# Inverter.net
KiCad netlist of a schematic drawn in Altium Designer
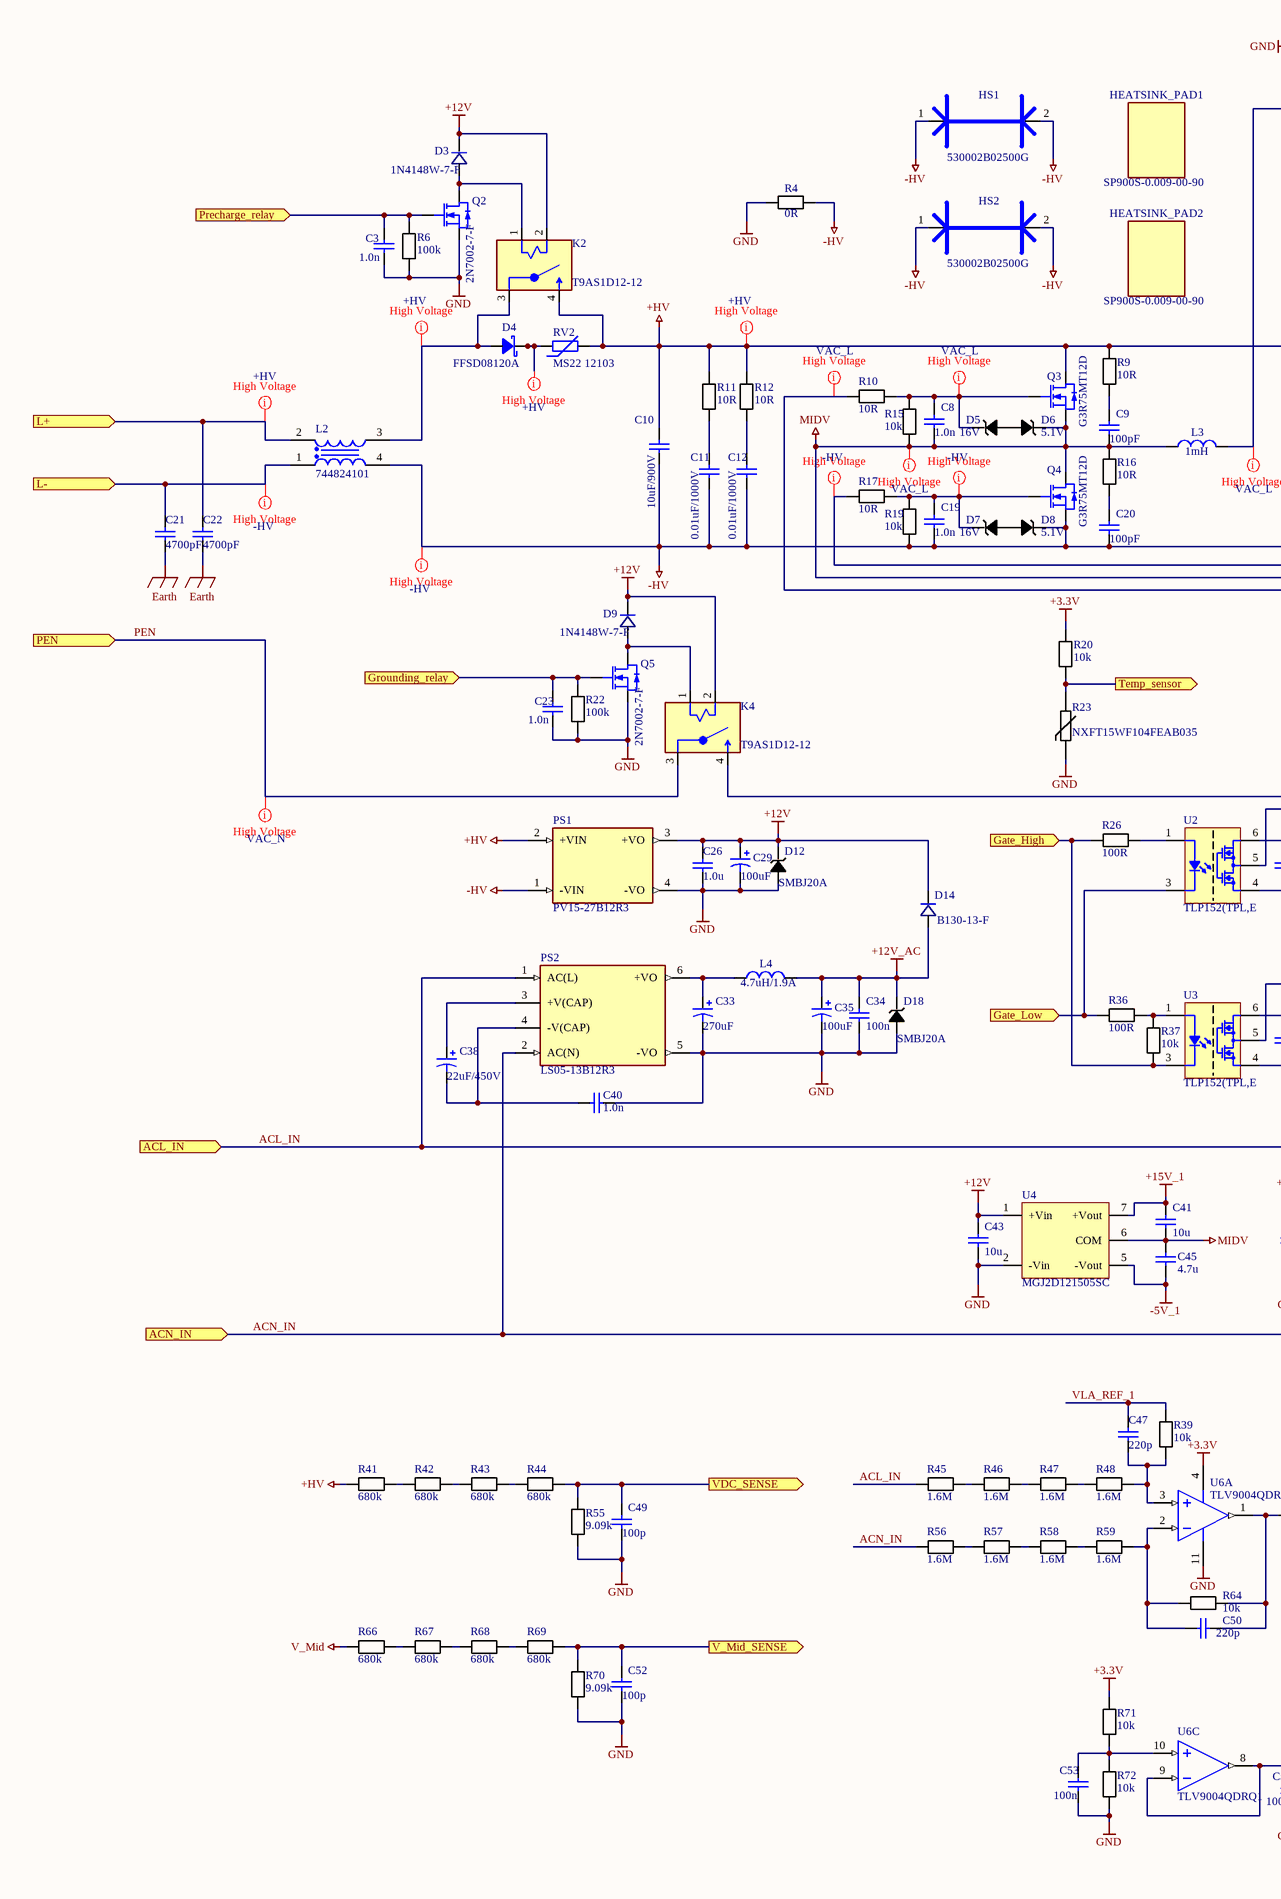
[diagram p0: Inverter.SchDoc, left]
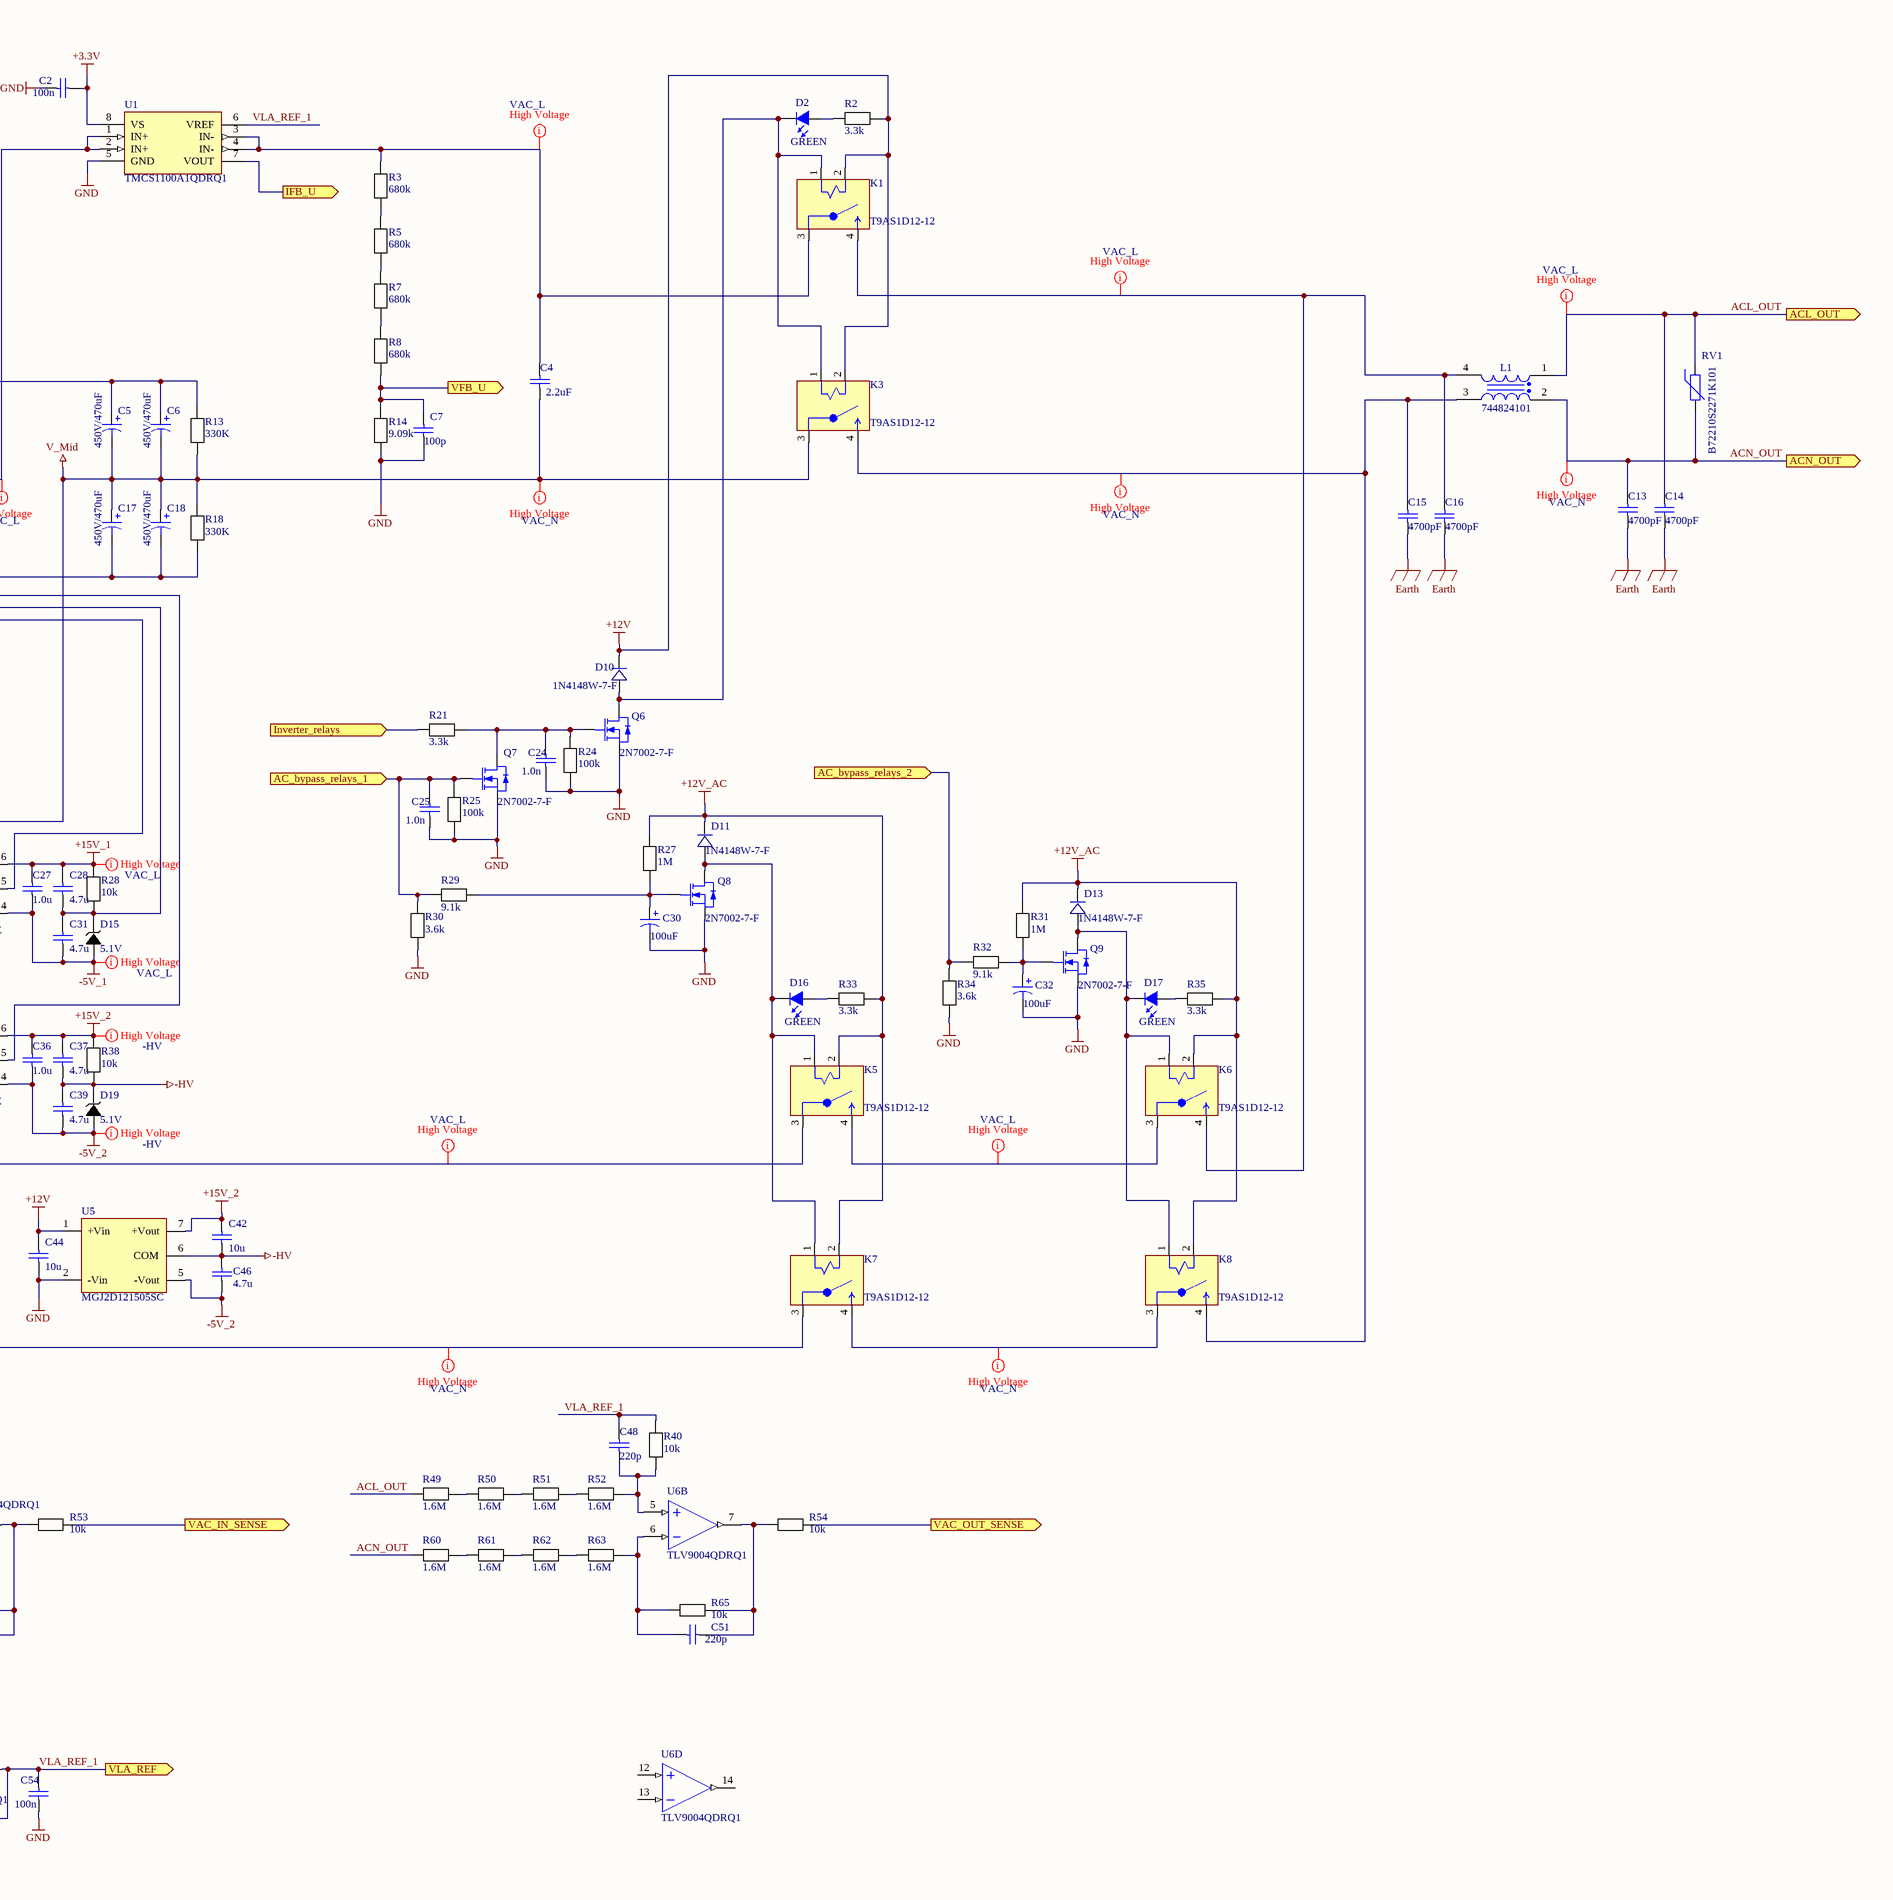
[diagram p1: Inverter.SchDoc, right]

(export (version "E")
  (design (tool "Eeschema 10.0.6"))
  (components
    (comp (ref "C2")
      (value "100n")
      (footprint "C0603")
      (description "Capacitor 100n 0603 +-10% 50V")
      (fields
        (field (name "PART NUMBER") "CAP_YAG_CC0603KRX7R9BB104_X7R")
        (field (name "MPN") "CC0603KRX7R9BB104")
      )
      (libsource (lib "Cap_Yag_0603_X7R_50_10%$") (part "CAP_YAG_CC0603KRX7R9BB104_X7R"))
    )
    (comp (ref "C3")
      (value "1.0n")
      (footprint "C0603")
      (description "Capacitor 1.0n 0603 +-10% 50V")
      (fields (field (name "PART NUMBER") "CAP_YAG_CC0603KRNPO9BN102_NPO") (field (name "MFR") "Yageo"))
      (libsource (lib "Cap_Yag_0603_NPO_50_10%$") (part "CAP_YAG_CC0603KRNPO9BN102_NPO"))
    )
    (comp (ref "C4")
      (value "2.2uF")
      (footprint "B32674")
      (fields (field (name "MPN") "B32674D6225K") (field (name "MFR") "EPCOS / TDK"))
      (libsource (lib "RCL") (part "CAP"))
    )
    (comp (ref "C5")
      (value "450V/470uF")
      (footprint "CAP_B43640B5477M000")
      (description "Aluminium Electrolytic Capacitors - Snap In 450VDC 470uF 20% PVC STD 6.3mm Term")
      (fields (field (name "MPN") "B43640B5477M000") (field (name "MFR") "EPCOS / TDK"))
      (libsource (lib "Miscellaneous Devices") (part "Cap Pol1"))
    )
    (comp (ref "C6")
      (value "450V/470uF")
      (footprint "CAP_B43640B5477M000")
      (description "Aluminium Electrolytic Capacitors - Snap In 450VDC 470uF 20% PVC STD 6.3mm Term")
      (fields (field (name "MPN") "B43640B5477M000") (field (name "MFR") "EPCOS / TDK"))
      (libsource (lib "Miscellaneous Devices") (part "Cap Pol1"))
    )
    (comp (ref "C7")
      (value "100p")
      (footprint "C0603")
      (description "Capacitor 100p 0603 +-10% 50V")
      (fields (field (name "PART NUMBER") "CAP_YAG_CC0603KRNPO9BN101_NPO") (field (name "MFR") "Yageo"))
      (libsource (lib "Cap_Yag_0603_NPO_50_10%$") (part "CAP_YAG_CC0603KRNPO9BN101_NPO"))
    )
    (comp (ref "C8")
      (value "1.0n")
      (footprint "C0603")
      (description "Capacitor 1.0n 0603 +-10% 50V")
      (fields (field (name "PART NUMBER") "CAP_YAG_CC0603KRNPO9BN102_NPO") (field (name "MFR") "Yageo"))
      (libsource (lib "Cap_Yag_0603_NPO_50_10%$") (part "CAP_YAG_CC0603KRNPO9BN102_NPO"))
    )
    (comp (ref "C9")
      (value "100pF")
      (footprint "C1210")
      (description "Capacitor 100p 1210 +-5% 1kV")
      (fields (field (name "MPN") "VJ1210A101JXGAT5Z") (field (name "MFR") "Vishay"))
      (libsource (lib "RCL") (part "CAP"))
    )
    (comp (ref "C10")
      (value "10uF/900V")
      (footprint "MKP1848C61090KK2")
      (description "CAP FILM 10UF 10% 900VDC")
      (fields (field (name "MPN") "MKP1848C61090KK2") (field (name "MFR") "Vishay / Roederstein"))
      (libsource (lib "RCL") (part "CAP"))
    )
    (comp (ref "C11")
      (value "0.01uF/1000V")
      (footprint "C1206")
      (description "0.01uF ±10% 1000V")
      (fields (field (name "MPN") "GRM31CR73A103KW03L") (field (name "MFR") "Murata"))
      (libsource (lib "RCL") (part "CAP"))
    )
    (comp (ref "C12")
      (value "0.01uF/1000V")
      (footprint "C1206")
      (description "0.01uF ±10% 1000V")
      (fields (field (name "MPN") "GRM31CR73A103KW03L") (field (name "MFR") "Murata"))
      (libsource (lib "RCL") (part "CAP"))
    )
    (comp (ref "C13")
      (value "4700pF")
      (footprint "CAP_C947U472MZVDBA7317")
      (description "4700pF ±20% 440VAC Ceramic Capacitor")
      (fields (field (name "MPN") "C947U472MZVDBA7317") (field (name "MFR") "KEMET"))
      (libsource (lib "RCL") (part "CAP"))
    )
    (comp (ref "C14")
      (value "4700pF")
      (footprint "CAP_C947U472MZVDBA7317")
      (description "4700pF ±20% 440VAC Ceramic Capacitor")
      (fields (field (name "MPN") "C947U472MZVDBA7317") (field (name "MFR") "KEMET"))
      (libsource (lib "RCL") (part "CAP"))
    )
    (comp (ref "C15")
      (value "4700pF")
      (footprint "CAP_C947U472MZVDBA7317")
      (description "4700pF ±20% 440VAC Ceramic Capacitor")
      (fields (field (name "MPN") "C947U472MZVDBA7317") (field (name "MFR") "KEMET"))
      (libsource (lib "RCL") (part "CAP"))
    )
    (comp (ref "C16")
      (value "4700pF")
      (footprint "CAP_C947U472MZVDBA7317")
      (description "4700pF ±20% 440VAC Ceramic Capacitor")
      (fields (field (name "MPN") "C947U472MZVDBA7317") (field (name "MFR") "KEMET"))
      (libsource (lib "RCL") (part "CAP"))
    )
    (comp (ref "C17")
      (value "450V/470uF")
      (footprint "CAP_B43640B5477M000")
      (description "Aluminium Electrolytic Capacitors - Snap In 450VDC 470uF 20% PVC STD 6.3mm Term")
      (fields (field (name "MPN") "B43640B5477M000") (field (name "MFR") "EPCOS / TDK"))
      (libsource (lib "Miscellaneous Devices") (part "Cap Pol1"))
    )
    (comp (ref "C18")
      (value "450V/470uF")
      (footprint "CAP_B43640B5477M000")
      (description "Aluminium Electrolytic Capacitors - Snap In 450VDC 470uF 20% PVC STD 6.3mm Term")
      (fields (field (name "MPN") "B43640B5477M000") (field (name "MFR") "EPCOS / TDK"))
      (libsource (lib "Miscellaneous Devices") (part "Cap Pol1"))
    )
    (comp (ref "C19")
      (value "1.0n")
      (footprint "C0603")
      (description "Capacitor 1.0n 0603 +-10% 50V")
      (fields (field (name "PART NUMBER") "CAP_YAG_CC0603KRNPO9BN102_NPO") (field (name "MFR") "Yageo"))
      (libsource (lib "Cap_Yag_0603_NPO_50_10%$") (part "CAP_YAG_CC0603KRNPO9BN102_NPO"))
    )
    (comp (ref "C20")
      (value "100pF")
      (footprint "C1210")
      (description "Capacitor 100p 1210 +-5% 1kV")
      (fields (field (name "MPN") "VJ1210A101JXGAT5Z") (field (name "MFR") "Vishay"))
      (libsource (lib "RCL") (part "CAP"))
    )
    (comp (ref "C21")
      (value "4700pF")
      (footprint "CAP_C947U472MZVDBA7317")
      (description "4700pF ±20% 440VAC Ceramic Capacitor")
      (fields (field (name "MPN") "C947U472MZVDBA7317") (field (name "MFR") "KEMET"))
      (libsource (lib "RCL") (part "CAP"))
    )
    (comp (ref "C22")
      (value "4700pF")
      (footprint "CAP_C947U472MZVDBA7317")
      (description "4700pF ±20% 440VAC Ceramic Capacitor")
      (fields (field (name "MPN") "C947U472MZVDBA7317") (field (name "MFR") "KEMET"))
      (libsource (lib "RCL") (part "CAP"))
    )
    (comp (ref "C23")
      (value "1.0n")
      (footprint "C0603")
      (description "Capacitor 1.0n 0603 +-10% 50V")
      (fields (field (name "PART NUMBER") "CAP_YAG_CC0603KRNPO9BN102_NPO") (field (name "MFR") "Yageo"))
      (libsource (lib "Cap_Yag_0603_NPO_50_10%$") (part "CAP_YAG_CC0603KRNPO9BN102_NPO"))
    )
    (comp (ref "C24")
      (value "1.0n")
      (footprint "C0603")
      (description "Capacitor 1.0n 0603 +-10% 50V")
      (fields (field (name "PART NUMBER") "CAP_YAG_CC0603KRNPO9BN102_NPO") (field (name "MFR") "Yageo"))
      (libsource (lib "Cap_Yag_0603_NPO_50_10%$") (part "CAP_YAG_CC0603KRNPO9BN102_NPO"))
    )
    (comp (ref "C25")
      (value "1.0n")
      (footprint "C0603")
      (description "Capacitor 1.0n 0603 +-10% 50V")
      (fields (field (name "PART NUMBER") "CAP_YAG_CC0603KRNPO9BN102_NPO") (field (name "MFR") "Yageo"))
      (libsource (lib "Cap_Yag_0603_NPO_50_10%$") (part "CAP_YAG_CC0603KRNPO9BN102_NPO"))
    )
    (comp (ref "C26")
      (value "1.0u")
      (footprint "C0603")
      (description "Capacitor 1.0u 0603 +-10% 50V")
      (fields (field (name "PART NUMBER") "CAP_YAG_CC0603KRX7R9BB105_X7R") (field (name "MFR") "Yageo"))
      (libsource (lib "Cap_Yag_0603_X7R_50_10%$") (part "CAP_YAG_CC0603KRX7R9BB105_X7R"))
    )
    (comp (ref "C27")
      (value "1.0u")
      (footprint "C0603")
      (description "Capacitor 1.0u 0603 +-10% 25V")
      (fields (field (name "PART NUMBER") "CAP_YAG_CC0603KRX5R8BB105_X5R") (field (name "MFR") "Yageo"))
      (libsource (lib "Cap_Yag_0603_X5R_25_10%$") (part "CAP_YAG_CC0603KRX5R8BB105_X5R"))
    )
    (comp (ref "C28")
      (value "4.7u")
      (footprint "C1206")
      (description "Capacitor 4.7u 1206 +-10% 25V")
      (fields (field (name "MFR") "Yageo") (field (name "MPN") "CC1206KKX7R8BB475"))
      (libsource (lib "Inverter_2kW") (part "CAP_YAG_CC1206KKX7R8BB475"))
    )
    (comp (ref "C29")
      (value "100uF")
      (footprint "CAP_EEUFC1E101S")
      (description "CAP ALUM 100UF 20% 25V SMD")
      (fields (field (name "MPN") "EEU-FC1E101S") (field (name "MFR") "Panasonic"))
      (libsource (lib "Miscellaneous Devices") (part "Cap Pol1"))
    )
    (comp (ref "C30")
      (value "100uF")
      (footprint "CAP_EEUFC1E101S")
      (description "CAP ALUM 100UF 20% 25V SMD")
      (fields (field (name "MPN") "EEU-FC1E101S") (field (name "MFR") "Panasonic"))
      (libsource (lib "Miscellaneous Devices") (part "Cap Pol1"))
    )
    (comp (ref "C31")
      (value "4.7u")
      (footprint "C1206")
      (description "Capacitor 4.7u 1206 +-10% 25V")
      (fields (field (name "MFR") "Yageo") (field (name "MPN") "CC1206KKX7R8BB475"))
      (libsource (lib "Inverter_2kW") (part "CAP_YAG_CC1206KKX7R8BB475"))
    )
    (comp (ref "C32")
      (value "100uF")
      (footprint "CAP_EEUFC1E101S")
      (description "CAP ALUM 100UF 20% 25V SMD")
      (fields (field (name "MPN") "EEU-FC1E101S") (field (name "MFR") "Panasonic"))
      (libsource (lib "Miscellaneous Devices") (part "Cap Pol1"))
    )
    (comp (ref "C33")
      (value "270uF")
      (footprint "CAP_EEU-FK1E271B")
      (description "CAP ALUM 270UF 20% 25V SMD")
      (fields (field (name "MPN") "EEU-FC1E271B") (field (name "MFR") "Panasonic"))
      (libsource (lib "Miscellaneous Devices") (part "Cap Pol1"))
    )
    (comp (ref "C34")
      (value "100n")
      (footprint "C0603")
      (description "Capacitor 100n 0603 +-10% 50V")
      (fields
        (field (name "PART NUMBER") "CAP_YAG_CC0603KRX7R9BB104_X7R")
        (field (name "MPN") "CC0603KRX7R9BB104")
      )
      (libsource (lib "Cap_Yag_0603_X7R_50_10%$") (part "CAP_YAG_CC0603KRX7R9BB104_X7R"))
    )
    (comp (ref "C35")
      (value "100uF")
      (footprint "CAP_EEUFC1E101S")
      (description "CAP ALUM 100UF 20% 25V SMD")
      (fields (field (name "MPN") "EEU-FC1E101S") (field (name "MFR") "Panasonic"))
      (libsource (lib "Miscellaneous Devices") (part "Cap Pol1"))
    )
    (comp (ref "C36")
      (value "1.0u")
      (footprint "C0603")
      (description "Capacitor 1.0u 0603 +-10% 25V")
      (fields (field (name "PART NUMBER") "CAP_YAG_CC0603KRX5R8BB105_X5R") (field (name "MFR") "Yageo"))
      (libsource (lib "Cap_Yag_0603_X5R_25_10%$") (part "CAP_YAG_CC0603KRX5R8BB105_X5R"))
    )
    (comp (ref "C37")
      (value "4.7u")
      (footprint "C1206")
      (description "Capacitor 4.7u 1206 +-10% 25V")
      (fields (field (name "MFR") "Yageo") (field (name "MPN") "CC1206KKX7R8BB475"))
      (libsource (lib "Inverter_2kW") (part "CAP_YAG_CC1206KKX7R8BB475"))
    )
    (comp (ref "C38")
      (value "22uF/450V")
      (footprint "CAP_450BXW22MEFR12.5X20")
      (description "CAP ALUM 22UF 20% 450V SMD")
      (fields (field (name "MPN") "450BXW22MEFR12.5X20") (field (name "MFR") "Rubycon"))
      (libsource (lib "Miscellaneous Devices") (part "Cap Pol1"))
    )
    (comp (ref "C39")
      (value "4.7u")
      (footprint "C1206")
      (description "Capacitor 4.7u 1206 +-10% 25V")
      (fields (field (name "MFR") "Yageo") (field (name "MPN") "CC1206KKX7R8BB475"))
      (libsource (lib "Inverter_2kW") (part "CAP_YAG_CC1206KKX7R8BB475"))
    )
    (comp (ref "C40")
      (value "1.0n")
      (footprint "C0603")
      (description "Capacitor 1.0n 0603 +-10% 50V")
      (fields (field (name "PART NUMBER") "CAP_YAG_CC0603KRNPO9BN102_NPO") (field (name "MFR") "Yageo"))
      (libsource (lib "Cap_Yag_0603_NPO_50_10%$") (part "CAP_YAG_CC0603KRNPO9BN102_NPO"))
    )
    (comp (ref "C41")
      (value "10u")
      (footprint "C1206")
      (description "Capacitor 10u 1206 +-10% 25V")
      (fields (field (name "MFR") "Yageo") (field (name "MPN") "CC1206KKX7R8BB106"))
      (libsource (lib "Inverter_2kW") (part "CAP_YAG_CC1206KKX7R8BB106"))
    )
    (comp (ref "C42")
      (value "10u")
      (footprint "C1206")
      (description "Capacitor 10u 1206 +-10% 25V")
      (fields (field (name "MFR") "Yageo") (field (name "MPN") "CC1206KKX7R8BB106"))
      (libsource (lib "Inverter_2kW") (part "CAP_YAG_CC1206KKX7R8BB106"))
    )
    (comp (ref "C43")
      (value "10u")
      (footprint "C1206")
      (description "Capacitor 10u 1206 +-10% 25V")
      (fields (field (name "MFR") "Yageo") (field (name "MPN") "CC1206KKX7R8BB106"))
      (libsource (lib "Inverter_2kW") (part "CAP_YAG_CC1206KKX7R8BB106"))
    )
    (comp (ref "C44")
      (value "10u")
      (footprint "C1206")
      (description "Capacitor 10u 1206 +-10% 25V")
      (fields (field (name "MFR") "Yageo") (field (name "MPN") "CC1206KKX7R8BB106"))
      (libsource (lib "Inverter_2kW") (part "CAP_YAG_CC1206KKX7R8BB106"))
    )
    (comp (ref "C45")
      (value "4.7u")
      (footprint "C1206")
      (description "Capacitor 4.7u 1206 +-10% 25V")
      (fields (field (name "MFR") "Yageo") (field (name "MPN") "CC1206KKX7R8BB475"))
      (libsource (lib "Inverter_2kW") (part "CAP_YAG_CC1206KKX7R8BB475"))
    )
    (comp (ref "C46")
      (value "4.7u")
      (footprint "C1206")
      (description "Capacitor 4.7u 1206 +-10% 25V")
      (fields (field (name "MFR") "Yageo") (field (name "MPN") "CC1206KKX7R8BB475"))
      (libsource (lib "Inverter_2kW") (part "CAP_YAG_CC1206KKX7R8BB475"))
    )
    (comp (ref "C47")
      (value "220p")
      (footprint "C0603")
      (description "Capacitor 220p 0603 +-10% 50V")
      (fields (field (name "PART NUMBER") "CAP_YAG_CC0603KRNPO9BN221_NPO") (field (name "MFR") "Yageo"))
      (libsource (lib "Cap_Yag_0603_NPO_50_10%$") (part "CAP_YAG_CC0603KRNPO9BN221_NPO"))
    )
    (comp (ref "C48")
      (value "220p")
      (footprint "C0603")
      (description "Capacitor 220p 0603 +-10% 50V")
      (fields (field (name "PART NUMBER") "CAP_YAG_CC0603KRNPO9BN221_NPO") (field (name "MFR") "Yageo"))
      (libsource (lib "Cap_Yag_0603_NPO_50_10%$") (part "CAP_YAG_CC0603KRNPO9BN221_NPO"))
    )
    (comp (ref "C49")
      (value "100p")
      (footprint "C0603")
      (description "Capacitor 100p 0603 +-10% 50V")
      (fields (field (name "PART NUMBER") "CAP_YAG_CC0603KRNPO9BN101_NPO") (field (name "MFR") "Yageo"))
      (libsource (lib "Cap_Yag_0603_NPO_50_10%$") (part "CAP_YAG_CC0603KRNPO9BN101_NPO"))
    )
    (comp (ref "C50")
      (value "220p")
      (footprint "C0603")
      (description "Capacitor 220p 0603 +-10% 50V")
      (fields (field (name "PART NUMBER") "CAP_YAG_CC0603KRNPO9BN221_NPO") (field (name "MFR") "Yageo"))
      (libsource (lib "Cap_Yag_0603_NPO_50_10%$") (part "CAP_YAG_CC0603KRNPO9BN221_NPO"))
    )
    (comp (ref "C51")
      (value "220p")
      (footprint "C0603")
      (description "Capacitor 220p 0603 +-10% 50V")
      (fields (field (name "PART NUMBER") "CAP_YAG_CC0603KRNPO9BN221_NPO") (field (name "MFR") "Yageo"))
      (libsource (lib "Cap_Yag_0603_NPO_50_10%$") (part "CAP_YAG_CC0603KRNPO9BN221_NPO"))
    )
    (comp (ref "C52")
      (value "100p")
      (footprint "C0603")
      (description "Capacitor 100p 0603 +-10% 50V")
      (fields (field (name "PART NUMBER") "CAP_YAG_CC0603KRNPO9BN101_NPO") (field (name "MFR") "Yageo"))
      (libsource (lib "Cap_Yag_0603_NPO_50_10%$") (part "CAP_YAG_CC0603KRNPO9BN101_NPO"))
    )
    (comp (ref "C53")
      (value "100n")
      (footprint "C0603")
      (description "Capacitor 100n 0603 +-10% 50V")
      (fields
        (field (name "PART NUMBER") "CAP_YAG_CC0603KRX7R9BB104_X7R")
        (field (name "MPN") "CC0603KRX7R9BB104")
      )
      (libsource (lib "Cap_Yag_0603_X7R_50_10%$") (part "CAP_YAG_CC0603KRX7R9BB104_X7R"))
    )
    (comp (ref "C54")
      (value "100n")
      (footprint "C0603")
      (description "Capacitor 100n 0603 +-10% 50V")
      (fields
        (field (name "PART NUMBER") "CAP_YAG_CC0603KRX7R9BB104_X7R")
        (field (name "MPN") "CC0603KRX7R9BB104")
      )
      (libsource (lib "Cap_Yag_0603_X7R_50_10%$") (part "CAP_YAG_CC0603KRX7R9BB104_X7R"))
    )
    (comp (ref "D2")
      (value "GREEN")
      (footprint "LED0805")
      (description "SMD Surface Mount LED, 5 mA")
      (fields (field (name "MPN") "VCDG1112H-4BY3C-TR") (field (name "MFR") "Stanley Electric"))
      (libsource (lib "Inverter_2kW") (part "LED_SMD"))
    )
    (comp (ref "D3")
      (value "1N4148W-7-F")
      (footprint "SOD123")
      (description "Diodes - General Purpose, Power, Switching SURFACE MOUNT FAST SWITCHING DIODE")
      (fields (field (name "MFR") "Diodes Incorporated"))
      (libsource (lib "EnergyMeter") (part "1N4148W"))
    )
    (comp (ref "D4")
      (value "FFSD08120A")
      (footprint "DPAK-3")
      (description "Schottky Diodes & Rectifiers 1200V 8A SIC SBD")
      (fields (field (name "MFR") "onsemi"))
      (libsource (lib "Inverter_2kW") (part "FFSD08120A"))
    )
    (comp (ref "D5")
      (value "16V")
      (footprint "SOD323")
      (description "Zener Diodes 16V 300mW 5%")
      (fields (field (name "MPN") "BZX384-C16,115") (field (name "MFR") "Nexperia"))
      (libsource (lib "Inverter_2kW") (part "ZenerDiode"))
    )
    (comp (ref "D6")
      (value "5.1V")
      (footprint "SOD323")
      (description "Zener Diodes 5.1V 300mW 5%")
      (fields (field (name "MPN") "BZX384-C5V1,115") (field (name "MFR") "Nexperia"))
      (libsource (lib "Inverter_2kW") (part "ZenerDiode"))
    )
    (comp (ref "D7")
      (value "16V")
      (footprint "SOD323")
      (description "Zener Diodes 16V 300mW 5%")
      (fields (field (name "MPN") "BZX384-C16,115") (field (name "MFR") "Nexperia"))
      (libsource (lib "Inverter_2kW") (part "ZenerDiode"))
    )
    (comp (ref "D8")
      (value "5.1V")
      (footprint "SOD323")
      (description "Zener Diodes 5.1V 300mW 5%")
      (fields (field (name "MPN") "BZX384-C5V1,115") (field (name "MFR") "Nexperia"))
      (libsource (lib "Inverter_2kW") (part "ZenerDiode"))
    )
    (comp (ref "D9")
      (value "1N4148W-7-F")
      (footprint "SOD123")
      (description "Diodes - General Purpose, Power, Switching SURFACE MOUNT FAST SWITCHING DIODE")
      (fields (field (name "MFR") "Diodes Incorporated"))
      (libsource (lib "EnergyMeter") (part "1N4148W"))
    )
    (comp (ref "D10")
      (value "1N4148W-7-F")
      (footprint "SOD123")
      (description "Diodes - General Purpose, Power, Switching SURFACE MOUNT FAST SWITCHING DIODE")
      (fields (field (name "MFR") "Diodes Incorporated"))
      (libsource (lib "EnergyMeter") (part "1N4148W"))
    )
    (comp (ref "D11")
      (value "1N4148W-7-F")
      (footprint "SOD123")
      (description "Diodes - General Purpose, Power, Switching SURFACE MOUNT FAST SWITCHING DIODE")
      (fields (field (name "MFR") "Diodes Incorporated"))
      (libsource (lib "EnergyMeter") (part "1N4148W"))
    )
    (comp (ref "D12")
      (value "SMBJ20A")
      (footprint "DO-214AA2")
      (description "ESD Suppressors / TVS Diodes 600W, 23.4V, 5%, Unidirectional, TVS")
      (fields (field (name "MFR") "Taiwan Semiconductor"))
      (libsource (lib "Charger") (part "ZM4746A-GS08"))
    )
    (comp (ref "D13")
      (value "1N4148W-7-F")
      (footprint "SOD123")
      (description "Diodes - General Purpose, Power, Switching SURFACE MOUNT FAST SWITCHING DIODE")
      (fields (field (name "MFR") "Diodes Incorporated"))
      (libsource (lib "EnergyMeter") (part "1N4148W"))
    )
    (comp (ref "D14")
      (value "B130-13-F")
      (footprint "DO-214AC")
      (description "Schottky Diodes & Rectifiers 30V 1A")
      (fields (field (name "MFR") "Diodes Incorporated"))
      (libsource (lib "Inverter_2kW") (part "B130-13-F"))
    )
    (comp (ref "D15")
      (value "5.1V")
      (footprint "SOD323")
      (description "Zener Diodes 5.1V 300mW 5%")
      (fields (field (name "MPN") "BZX384-C5V1,115") (field (name "MFR") "Nexperia"))
      (libsource (lib "Inverter_2kW") (part "ZenerDiode"))
    )
    (comp (ref "D16")
      (value "GREEN")
      (footprint "LED0805")
      (description "SMD Surface Mount LED, 5 mA")
      (fields (field (name "MPN") "VCDG1112H-4BY3C-TR") (field (name "MFR") "Stanley Electric"))
      (libsource (lib "Inverter_2kW") (part "LED_SMD"))
    )
    (comp (ref "D17")
      (value "GREEN")
      (footprint "LED0805")
      (description "SMD Surface Mount LED, 5 mA")
      (fields (field (name "MPN") "VCDG1112H-4BY3C-TR") (field (name "MFR") "Stanley Electric"))
      (libsource (lib "Inverter_2kW") (part "LED_SMD"))
    )
    (comp (ref "D18")
      (value "SMBJ20A")
      (footprint "DO-214AA2")
      (description "ESD Suppressors / TVS Diodes 600W, 23.4V, 5%, Unidirectional, TVS")
      (fields (field (name "MFR") "Taiwan Semiconductor"))
      (libsource (lib "Charger") (part "ZM4746A-GS08"))
    )
    (comp (ref "D19")
      (value "5.1V")
      (footprint "SOD323")
      (description "Zener Diodes 5.1V 300mW 5%")
      (fields (field (name "MPN") "BZX384-C5V1,115") (field (name "MFR") "Nexperia"))
      (libsource (lib "Inverter_2kW") (part "ZenerDiode"))
    )
    (comp (ref "HEATSINK_PAD1")
      (value "SP900S-0.009-00-90")
      (footprint "SP900S-0.009-00-90")
      (description "Thermal Interface Products Sil-Pad, Low-Pressure, 0.009\" Thickness, 21.84x18.80mm, TSP1600S/900S")
      (fields (field (name "MFR") "Bergquist Company"))
      (libsource (lib "Inverter_2kW") (part "SP900S-0.009-00-90"))
    )
    (comp (ref "HEATSINK_PAD2")
      (value "SP900S-0.009-00-90")
      (footprint "SP900S-0.009-00-90")
      (description "Thermal Interface Products Sil-Pad, Low-Pressure, 0.009\" Thickness, 21.84x18.80mm, TSP1600S/900S")
      (fields (field (name "MFR") "Bergquist Company"))
      (libsource (lib "Inverter_2kW") (part "SP900S-0.009-00-90"))
    )
    (comp (ref "HS1")
      (value "530002B02500G")
      (footprint "530002B02500G")
      (fields (field (name "MFR") "Aavid"))
      (libsource (lib "Inverter_2kW") (part "530002B02500G"))
    )
    (comp (ref "HS2")
      (value "530002B02500G")
      (footprint "530002B02500G")
      (fields (field (name "MFR") "Aavid"))
      (libsource (lib "Inverter_2kW") (part "530002B02500G"))
    )
    (comp (ref "K1")
      (value "T9AS1D12-12")
      (footprint "RELAY_T9AS1D12-12")
      (description "p&b Low Cost Pc Board Relay, Immersion Cleanable, 1 Form a _Spst-No_")
      (fields (field (name "MFR") "TE Connectivity"))
      (libsource (lib "Inverter_2kW") (part "T9AS1D12-12"))
    )
    (comp (ref "K2")
      (value "T9AS1D12-12")
      (footprint "RELAY_T9AS1D12-12")
      (description "p&b Low Cost Pc Board Relay, Immersion Cleanable, 1 Form a _Spst-No_")
      (fields (field (name "MFR") "TE Connectivity"))
      (libsource (lib "Inverter_2kW") (part "T9AS1D12-12"))
    )
    (comp (ref "K3")
      (value "T9AS1D12-12")
      (footprint "RELAY_T9AS1D12-12")
      (description "p&b Low Cost Pc Board Relay, Immersion Cleanable, 1 Form a _Spst-No_")
      (fields (field (name "MFR") "TE Connectivity"))
      (libsource (lib "Inverter_2kW") (part "T9AS1D12-12"))
    )
    (comp (ref "K4")
      (value "T9AS1D12-12")
      (footprint "RELAY_T9AS1D12-12")
      (description "p&b Low Cost Pc Board Relay, Immersion Cleanable, 1 Form a _Spst-No_")
      (fields (field (name "MFR") "TE Connectivity"))
      (libsource (lib "Inverter_2kW") (part "T9AS1D12-12"))
    )
    (comp (ref "K5")
      (value "T9AS1D12-12")
      (footprint "RELAY_T9AS1D12-12")
      (description "p&b Low Cost Pc Board Relay, Immersion Cleanable, 1 Form a _Spst-No_")
      (fields (field (name "MFR") "TE Connectivity"))
      (libsource (lib "Inverter_2kW") (part "T9AS1D12-12"))
    )
    (comp (ref "K6")
      (value "T9AS1D12-12")
      (footprint "RELAY_T9AS1D12-12")
      (description "p&b Low Cost Pc Board Relay, Immersion Cleanable, 1 Form a _Spst-No_")
      (fields (field (name "MFR") "TE Connectivity"))
      (libsource (lib "Inverter_2kW") (part "T9AS1D12-12"))
    )
    (comp (ref "K7")
      (value "T9AS1D12-12")
      (footprint "RELAY_T9AS1D12-12")
      (description "p&b Low Cost Pc Board Relay, Immersion Cleanable, 1 Form a _Spst-No_")
      (fields (field (name "MFR") "TE Connectivity"))
      (libsource (lib "Inverter_2kW") (part "T9AS1D12-12"))
    )
    (comp (ref "K8")
      (value "T9AS1D12-12")
      (footprint "RELAY_T9AS1D12-12")
      (description "p&b Low Cost Pc Board Relay, Immersion Cleanable, 1 Form a _Spst-No_")
      (fields (field (name "MFR") "TE Connectivity"))
      (libsource (lib "Inverter_2kW") (part "T9AS1D12-12"))
    )
    (comp (ref "L1")
      (value "1mH")
      (footprint "WE-CMB_Type L_L27.5W18.5H33")
      (description "WE-CMB Common Mode Power Line Choke, THT, Type L, 1mH, 10A, 7mOhm")
      (fields (field (name "MPN") "744824101") (field (name "MFR") "Wurth Elektronik"))
      (libsource (lib "WE-CMB") (part "744824101"))
    )
    (comp (ref "L2")
      (value "1mH")
      (footprint "WE-CMB_Type L_L27.5W18.5H33")
      (description "WE-CMB Common Mode Power Line Choke, THT, Type L, 1mH, 10A, 7mOhm")
      (fields (field (name "MPN") "744824101") (field (name "MFR") "Wurth Elektronik"))
      (libsource (lib "WE-CMB") (part "744824101"))
    )
    (comp (ref "L3")
      (value "1mH")
      (footprint "IND_FS-226060-2H305")
      (description "Custom Inductor with FS-226060-2H305")
      (fields (field (name "MPN") "Custom"))
      (libsource (lib "WirelessCharger") (part "Inductor"))
    )
    (comp (ref "L4")
      (value "4.7uH/1.9A")
      (footprint "IND_SRN3015C")
      (description "Power Inductors - SMD Ind,3x3x1.3mm,4.7uH20%,1.9A,shd")
      (fields (field (name "MPN") "SRN3015C-4R7M") (field (name "MFR") "Bourns"))
      (libsource (lib "WirelessCharger") (part "Inductor"))
    )
    (comp (ref "PS1")
      (value "PV15-27B12R3")
      (footprint "CONV_PV15-27B12R3")
      (description "Isolated Module DC DC Converter 1 Output 12V - - - 1A 100V - 1000V Input")
      (fields (field (name "MFR") "Mornsun America, LLC"))
      (libsource (lib "Inverter_2kW") (part "PV15-27B12R3"))
    )
    (comp (ref "PS2")
      (value "LS05-13B12R3")
      (footprint "CONV_LS05-13B12R3")
      (description "Enclosed AC DC Converters 1 Uitgang 12V 420mA 85 ~ 305 VAC, 70 ~ 430 VDC Input")
      (fields (field (name "MFR") "Mornsun America, LLC"))
      (libsource (lib "Inverter_2kW") (part "LS05-13B12R3"))
    )
    (comp (ref "Q2")
      (value "2N7002-7-F")
      (footprint "SOT23-3N")
      (description "MOSFET N-CH 60V 200MA SOT23-3")
      (fields (field (name "MFR") "Diodes Incorporated"))
      (libsource (lib "BidirectionalCharger") (part "MOSFET-N"))
    )
    (comp (ref "Q3")
      (value "G3R75MT12D")
      (footprint "TO247-3")
      (description "MOSFET 1200V 75mO TO-247-3 G3R SiC MOSFET")
      (fields (field (name "MFR") "GeneSiC Semiconductor"))
      (libsource (lib "") (part "MOSFET-N_1"))
    )
    (comp (ref "Q4")
      (value "G3R75MT12D")
      (footprint "TO247-3")
      (description "MOSFET 1200V 75mO TO-247-3 G3R SiC MOSFET")
      (fields (field (name "MFR") "GeneSiC Semiconductor"))
      (libsource (lib "") (part "MOSFET-N_1"))
    )
    (comp (ref "Q5")
      (value "2N7002-7-F")
      (footprint "SOT23-3N")
      (description "MOSFET N-CH 60V 200MA SOT23-3")
      (fields (field (name "MFR") "Diodes Incorporated"))
      (libsource (lib "BidirectionalCharger") (part "MOSFET-N"))
    )
    (comp (ref "Q6")
      (value "2N7002-7-F")
      (footprint "SOT23-3N")
      (description "MOSFET N-CH 60V 200MA SOT23-3")
      (fields (field (name "MFR") "Diodes Incorporated"))
      (libsource (lib "BidirectionalCharger") (part "MOSFET-N"))
    )
    (comp (ref "Q7")
      (value "2N7002-7-F")
      (footprint "SOT23-3N")
      (description "MOSFET N-CH 60V 200MA SOT23-3")
      (fields (field (name "MFR") "Diodes Incorporated"))
      (libsource (lib "BidirectionalCharger") (part "MOSFET-N"))
    )
    (comp (ref "Q8")
      (value "2N7002-7-F")
      (footprint "SOT23-3N")
      (description "MOSFET N-CH 60V 200MA SOT23-3")
      (fields (field (name "MFR") "Diodes Incorporated"))
      (libsource (lib "BidirectionalCharger") (part "MOSFET-N"))
    )
    (comp (ref "Q9")
      (value "2N7002-7-F")
      (footprint "SOT23-3N")
      (description "MOSFET N-CH 60V 200MA SOT23-3")
      (fields (field (name "MFR") "Diodes Incorporated"))
      (libsource (lib "BidirectionalCharger") (part "MOSFET-N"))
    )
    (comp (ref "R2")
      (value "3.3k")
      (footprint "R0603")
      (description "0.1W/ 3.3kohm±1%")
      (fields (field (name "MPN") "RC0603FR-073K3L") (field (name "MFR") "Yageo"))
      (libsource (lib "RCL") (part "RES"))
    )
    (comp (ref "R3")
      (value "680k")
      (footprint "R1206")
      (description "0.25W/ 680kohm±1%")
      (fields (field (name "MPN") "RC1206FR-07680KL") (field (name "MFR") "Yageo"))
      (libsource (lib "RCL") (part "RES"))
    )
    (comp (ref "R4")
      (value "0R")
      (footprint "R1206")
      (description "0.25W/ 0ohm±0.05%")
      (fields (field (name "MPN") "ERJ-8GEY0R00V") (field (name "MFR") "Panasonic"))
      (libsource (lib "RCL") (part "RES"))
    )
    (comp (ref "R5")
      (value "680k")
      (footprint "R1206")
      (description "0.25W/ 680kohm±1%")
      (fields (field (name "MPN") "RC1206FR-07680KL") (field (name "MFR") "Yageo"))
      (libsource (lib "RCL") (part "RES"))
    )
    (comp (ref "R6")
      (value "100k")
      (footprint "R0603")
      (description "0.1W/ 100kohm±1%")
      (fields (field (name "MPN") "RC0603FR-07100KL") (field (name "MFR") "Yageo"))
      (libsource (lib "RCL") (part "RES"))
    )
    (comp (ref "R7")
      (value "680k")
      (footprint "R1206")
      (description "0.25W/ 680kohm±1%")
      (fields (field (name "MPN") "RC1206FR-07680KL") (field (name "MFR") "Yageo"))
      (libsource (lib "RCL") (part "RES"))
    )
    (comp (ref "R8")
      (value "680k")
      (footprint "R1206")
      (description "0.25W/ 680kohm±1%")
      (fields (field (name "MPN") "RC1206FR-07680KL") (field (name "MFR") "Yageo"))
      (libsource (lib "RCL") (part "RES"))
    )
    (comp (ref "R9")
      (value "10R")
      (footprint "R1210")
      (description "10 Ohms ±1% 0.5W")
      (fields (field (name "MPN") "AC1210FR-0710RL") (field (name "MFR") "Yageo"))
      (libsource (lib "RCL") (part "RES"))
    )
    (comp (ref "R10")
      (value "10R")
      (footprint "R1210")
      (description "10 Ohms ±1% 0.5W")
      (fields (field (name "MPN") "AC1210FR-0710RL") (field (name "MFR") "Yageo"))
      (libsource (lib "RCL") (part "RES"))
    )
    (comp (ref "R11")
      (value "10R")
      (footprint "R1210")
      (description "10 Ohms ±1% 0.5W")
      (fields (field (name "MPN") "AC1210FR-0710RL") (field (name "MFR") "Yageo"))
      (libsource (lib "RCL") (part "RES"))
    )
    (comp (ref "R12")
      (value "10R")
      (footprint "R1210")
      (description "10 Ohms ±1% 0.5W")
      (fields (field (name "MPN") "AC1210FR-0710RL") (field (name "MFR") "Yageo"))
      (libsource (lib "RCL") (part "RES"))
    )
    (comp (ref "R13")
      (value "330K")
      (footprint "THT_R(3W)")
      (description "330 kOhm, 3W")
      (fields (field (name "MPN") "RR03J330KTB") (field (name "MFR") "TE Connectivity"))
      (libsource (lib "RCL") (part "RES"))
    )
    (comp (ref "R14")
      (value "9.09k")
      (footprint "R0603")
      (description "0.1W/ 9.09kohm±1%")
      (fields (field (name "MPN") "RC0603FR-079K09L") (field (name "MFR") "Yageo"))
      (libsource (lib "RCL") (part "RES"))
    )
    (comp (ref "R15")
      (value "10k")
      (footprint "R0603")
      (description "0.1W/ 10kohm±1%")
      (fields (field (name "MPN") "RC0603FR-0710KL") (field (name "MFR") "Yageo"))
      (libsource (lib "RCL") (part "RES"))
    )
    (comp (ref "R16")
      (value "10R")
      (footprint "R1210")
      (description "10 Ohms ±1% 0.5W")
      (fields (field (name "MPN") "AC1210FR-0710RL") (field (name "MFR") "Yageo"))
      (libsource (lib "RCL") (part "RES"))
    )
    (comp (ref "R17")
      (value "10R")
      (footprint "R1210")
      (description "10 Ohms ±1% 0.5W")
      (fields (field (name "MPN") "AC1210FR-0710RL") (field (name "MFR") "Yageo"))
      (libsource (lib "RCL") (part "RES"))
    )
    (comp (ref "R18")
      (value "330K")
      (footprint "THT_R(3W)")
      (description "330 kOhm, 3W")
      (fields (field (name "MPN") "RR03J330KTB") (field (name "MFR") "TE Connectivity"))
      (libsource (lib "RCL") (part "RES"))
    )
    (comp (ref "R19")
      (value "10k")
      (footprint "R0603")
      (description "0.1W/ 10kohm±1%")
      (fields (field (name "MPN") "RC0603FR-0710KL") (field (name "MFR") "Yageo"))
      (libsource (lib "RCL") (part "RES"))
    )
    (comp (ref "R20")
      (value "10k")
      (footprint "R0603")
      (description "0.1W/ 10kohm±1%")
      (fields (field (name "MPN") "RC0603FR-0710KL") (field (name "MFR") "Yageo"))
      (libsource (lib "RCL") (part "RES"))
    )
    (comp (ref "R21")
      (value "3.3k")
      (footprint "R0603")
      (description "0.1W/ 3.3kohm±1%")
      (fields (field (name "MPN") "RC0603FR-073K3L") (field (name "MFR") "Yageo"))
      (libsource (lib "RCL") (part "RES"))
    )
    (comp (ref "R22")
      (value "100k")
      (footprint "R0603")
      (description "0.1W/ 100kohm±1%")
      (fields (field (name "MPN") "RC0603FR-07100KL") (field (name "MFR") "Yageo"))
      (libsource (lib "RCL") (part "RES"))
    )
    (comp (ref "R23")
      (value "NXFT15WF104FEAB035")
      (footprint "NTC_Sensor")
      (description "NTC (Negative Temperature Coefficient) Thermistors")
      (fields (field (name "MFR") "Murata"))
      (libsource (lib "GDS_RESISTOR") (part "NTC 100K 1% 0805 0.1W_1"))
    )
    (comp (ref "R24")
      (value "100k")
      (footprint "R0603")
      (description "0.1W/ 100kohm±1%")
      (fields (field (name "MPN") "RC0603FR-07100KL") (field (name "MFR") "Yageo"))
      (libsource (lib "RCL") (part "RES"))
    )
    (comp (ref "R25")
      (value "100k")
      (footprint "R0603")
      (description "0.1W/ 100kohm±1%")
      (fields (field (name "MPN") "RC0603FR-07100KL") (field (name "MFR") "Yageo"))
      (libsource (lib "RCL") (part "RES"))
    )
    (comp (ref "R26")
      (value "100R")
      (footprint "R0603")
      (description "0.1W/ 100ohm±1%")
      (fields (field (name "MPN") "RC0603FR-07100RL") (field (name "MFR") "Yageo"))
      (libsource (lib "RCL") (part "RES"))
    )
    (comp (ref "R27")
      (value "1M")
      (footprint "R0603")
      (description "0.1W/ 1Mohm±1%")
      (fields (field (name "MPN") "RC0603FR-071ML") (field (name "MFR") "Yageo"))
      (libsource (lib "RCL") (part "RES"))
    )
    (comp (ref "R28")
      (value "10k")
      (footprint "R0603")
      (description "0.1W/ 10kohm±1%")
      (fields (field (name "MPN") "RC0603FR-0710KL") (field (name "MFR") "Yageo"))
      (libsource (lib "RCL") (part "RES"))
    )
    (comp (ref "R29")
      (value "9.1k")
      (footprint "R0603")
      (description "0.1W/ 9.1kohm±1%")
      (fields (field (name "MPN") "RC0603FR-079K1L") (field (name "MFR") "Yageo"))
      (libsource (lib "RCL") (part "RES"))
    )
    (comp (ref "R30")
      (value "3.6k")
      (footprint "R0603")
      (description "0.1W/ 3.6kohm±1%")
      (fields (field (name "MPN") "RC0603FR-073K6L") (field (name "MFR") "Yageo"))
      (libsource (lib "RCL") (part "RES"))
    )
    (comp (ref "R31")
      (value "1M")
      (footprint "R0603")
      (description "0.1W/ 1Mohm±1%")
      (fields (field (name "MPN") "RC0603FR-071ML") (field (name "MFR") "Yageo"))
      (libsource (lib "RCL") (part "RES"))
    )
    (comp (ref "R32")
      (value "9.1k")
      (footprint "R0603")
      (description "0.1W/ 9.1kohm±1%")
      (fields (field (name "MPN") "RC0603FR-079K1L") (field (name "MFR") "Yageo"))
      (libsource (lib "RCL") (part "RES"))
    )
    (comp (ref "R33")
      (value "3.3k")
      (footprint "R0603")
      (description "0.1W/ 3.3kohm±1%")
      (fields (field (name "MPN") "RC0603FR-073K3L") (field (name "MFR") "Yageo"))
      (libsource (lib "RCL") (part "RES"))
    )
    (comp (ref "R34")
      (value "3.6k")
      (footprint "R0603")
      (description "0.1W/ 3.6kohm±1%")
      (fields (field (name "MPN") "RC0603FR-073K6L") (field (name "MFR") "Yageo"))
      (libsource (lib "RCL") (part "RES"))
    )
    (comp (ref "R35")
      (value "3.3k")
      (footprint "R0603")
      (description "0.1W/ 3.3kohm±1%")
      (fields (field (name "MPN") "RC0603FR-073K3L") (field (name "MFR") "Yageo"))
      (libsource (lib "RCL") (part "RES"))
    )
    (comp (ref "R36")
      (value "100R")
      (footprint "R0603")
      (description "0.1W/ 100ohm±1%")
      (fields (field (name "MPN") "RC0603FR-07100RL") (field (name "MFR") "Yageo"))
      (libsource (lib "RCL") (part "RES"))
    )
    (comp (ref "R37")
      (value "10k")
      (footprint "R0603")
      (description "0.1W/ 10kohm±1%")
      (fields (field (name "MPN") "RC0603FR-0710KL") (field (name "MFR") "Yageo"))
      (libsource (lib "RCL") (part "RES"))
    )
    (comp (ref "R38")
      (value "10k")
      (footprint "R0603")
      (description "0.1W/ 10kohm±1%")
      (fields (field (name "MPN") "RC0603FR-0710KL") (field (name "MFR") "Yageo"))
      (libsource (lib "RCL") (part "RES"))
    )
    (comp (ref "R39")
      (value "10k")
      (footprint "R0603")
      (description "0.1W/ 10kohm±1%")
      (fields (field (name "MPN") "RC0603FR-0710KL") (field (name "MFR") "Yageo"))
      (libsource (lib "RCL") (part "RES"))
    )
    (comp (ref "R40")
      (value "10k")
      (footprint "R0603")
      (description "0.1W/ 10kohm±1%")
      (fields
        (field (name "MANUFACTURER PART NUMBER") "RC0603FR-0710KL")
        (field (name "MANUFACTURER") "Yageo")
      )
      (libsource (lib "RCL") (part "RES"))
    )
    (comp (ref "R41")
      (value "680k")
      (footprint "R1206")
      (description "0.25W/ 680kohm±1%")
      (fields (field (name "MPN") "RC1206FR-07680KL") (field (name "MFR") "Yageo"))
      (libsource (lib "RCL") (part "RES"))
    )
    (comp (ref "R42")
      (value "680k")
      (footprint "R1206")
      (description "0.25W/ 680kohm±1%")
      (fields (field (name "MPN") "RC1206FR-07680KL") (field (name "MFR") "Yageo"))
      (libsource (lib "RCL") (part "RES"))
    )
    (comp (ref "R43")
      (value "680k")
      (footprint "R1206")
      (description "0.25W/ 680kohm±1%")
      (fields (field (name "MPN") "RC1206FR-07680KL") (field (name "MFR") "Yageo"))
      (libsource (lib "RCL") (part "RES"))
    )
    (comp (ref "R44")
      (value "680k")
      (footprint "R1206")
      (description "0.25W/ 680kohm±1%")
      (fields (field (name "MPN") "RC1206FR-07680KL") (field (name "MFR") "Yageo"))
      (libsource (lib "RCL") (part "RES"))
    )
    (comp (ref "R45")
      (value "1.6M")
      (footprint "R1206")
      (description "0.25W/ 1.6Mohm±1%")
      (fields (field (name "MPN") "RC1206FR-071M6L") (field (name "MFR") "Yageo"))
      (libsource (lib "RCL") (part "RES"))
    )
    (comp (ref "R46")
      (value "1.6M")
      (footprint "R1206")
      (description "0.25W/ 1.6Mohm±1%")
      (fields (field (name "MPN") "RC1206FR-071M6L") (field (name "MFR") "Yageo"))
      (libsource (lib "RCL") (part "RES"))
    )
    (comp (ref "R47")
      (value "1.6M")
      (footprint "R1206")
      (description "0.25W/ 1.6Mohm±1%")
      (fields (field (name "MPN") "RC1206FR-071M6L") (field (name "MFR") "Yageo"))
      (libsource (lib "RCL") (part "RES"))
    )
    (comp (ref "R48")
      (value "1.6M")
      (footprint "R1206")
      (description "0.25W/ 1.6Mohm±1%")
      (fields (field (name "MPN") "RC1206FR-071M6L") (field (name "MFR") "Yageo"))
      (libsource (lib "RCL") (part "RES"))
    )
    (comp (ref "R49")
      (value "1.6M")
      (footprint "R1206")
      (description "0.25W/ 1.6Mohm±1%")
      (fields (field (name "MPN") "RC1206FR-071M6L") (field (name "MFR") "Yageo"))
      (libsource (lib "RCL") (part "RES"))
    )
    (comp (ref "R50")
      (value "1.6M")
      (footprint "R1206")
      (description "0.25W/ 1.6Mohm±1%")
      (fields (field (name "MPN") "RC1206FR-071M6L") (field (name "MFR") "Yageo"))
      (libsource (lib "RCL") (part "RES"))
    )
    (comp (ref "R51")
      (value "1.6M")
      (footprint "R1206")
      (description "0.25W/ 1.6Mohm±1%")
      (fields (field (name "MPN") "RC1206FR-071M6L") (field (name "MFR") "Yageo"))
      (libsource (lib "RCL") (part "RES"))
    )
    (comp (ref "R52")
      (value "1.6M")
      (footprint "R1206")
      (description "0.25W/ 1.6Mohm±1%")
      (fields (field (name "MPN") "RC1206FR-071M6L") (field (name "MFR") "Yageo"))
      (libsource (lib "RCL") (part "RES"))
    )
    (comp (ref "R53")
      (value "10k")
      (footprint "R0603")
      (description "0.1W/ 10kohm±1%")
      (fields (field (name "MPN") "RC0603FR-0710KL") (field (name "MFR") "Yageo"))
      (libsource (lib "RCL") (part "RES"))
    )
    (comp (ref "R54")
      (value "10k")
      (footprint "R0603")
      (description "0.1W/ 10kohm±1%")
      (fields (field (name "MPN") "RC0603FR-0710KL") (field (name "MFR") "Yageo"))
      (libsource (lib "RCL") (part "RES"))
    )
    (comp (ref "R55")
      (value "9.09k")
      (footprint "R0603")
      (description "0.1W/ 9.09kohm±1%")
      (fields (field (name "MPN") "RC0603FR-079K09L") (field (name "MFR") "Yageo"))
      (libsource (lib "RCL") (part "RES"))
    )
    (comp (ref "R56")
      (value "1.6M")
      (footprint "R1206")
      (description "0.25W/ 1.6Mohm±1%")
      (fields (field (name "MPN") "RC1206FR-071M6L") (field (name "MFR") "Yageo"))
      (libsource (lib "RCL") (part "RES"))
    )
    (comp (ref "R57")
      (value "1.6M")
      (footprint "R1206")
      (description "0.25W/ 1.6Mohm±1%")
      (fields (field (name "MPN") "RC1206FR-071M6L") (field (name "MFR") "Yageo"))
      (libsource (lib "RCL") (part "RES"))
    )
    (comp (ref "R58")
      (value "1.6M")
      (footprint "R1206")
      (description "0.25W/ 1.6Mohm±1%")
      (fields (field (name "MPN") "RC1206FR-071M6L") (field (name "MFR") "Yageo"))
      (libsource (lib "RCL") (part "RES"))
    )
    (comp (ref "R59")
      (value "1.6M")
      (footprint "R1206")
      (description "0.25W/ 1.6Mohm±1%")
      (fields (field (name "MPN") "RC1206FR-071M6L") (field (name "MFR") "Yageo"))
      (libsource (lib "RCL") (part "RES"))
    )
    (comp (ref "R60")
      (value "1.6M")
      (footprint "R1206")
      (description "0.25W/ 1.6Mohm±1%")
      (fields (field (name "MPN") "RC1206FR-071M6L") (field (name "MFR") "Yageo"))
      (libsource (lib "RCL") (part "RES"))
    )
    (comp (ref "R61")
      (value "1.6M")
      (footprint "R1206")
      (description "0.25W/ 1.6Mohm±1%")
      (fields (field (name "MPN") "RC1206FR-071M6L") (field (name "MFR") "Yageo"))
      (libsource (lib "RCL") (part "RES"))
    )
    (comp (ref "R62")
      (value "1.6M")
      (footprint "R1206")
      (description "0.25W/ 1.6Mohm±1%")
      (fields (field (name "MPN") "RC1206FR-071M6L") (field (name "MFR") "Yageo"))
      (libsource (lib "RCL") (part "RES"))
    )
    (comp (ref "R63")
      (value "1.6M")
      (footprint "R1206")
      (description "0.25W/ 1.6Mohm±1%")
      (fields (field (name "MPN") "RC1206FR-071M6L") (field (name "MFR") "Yageo"))
      (libsource (lib "RCL") (part "RES"))
    )
    (comp (ref "R64")
      (value "10k")
      (footprint "R0603")
      (description "0.1W/ 10kohm±1%")
      (fields (field (name "MPN") "RC0603FR-0710KL") (field (name "MFR") "Yageo"))
      (libsource (lib "RCL") (part "RES"))
    )
    (comp (ref "R65")
      (value "10k")
      (footprint "R0603")
      (description "0.1W/ 10kohm±1%")
      (fields (field (name "MPN") "RC0603FR-0710KL") (field (name "MFR") "Yageo"))
      (libsource (lib "RCL") (part "RES"))
    )
    (comp (ref "R66")
      (value "680k")
      (footprint "R1206")
      (description "0.25W/ 680kohm±1%")
      (fields (field (name "MPN") "RC1206FR-07680KL") (field (name "MFR") "Yageo"))
      (libsource (lib "RCL") (part "RES"))
    )
    (comp (ref "R67")
      (value "680k")
      (footprint "R1206")
      (description "0.25W/ 680kohm±1%")
      (fields (field (name "MPN") "RC1206FR-07680KL") (field (name "MFR") "Yageo"))
      (libsource (lib "RCL") (part "RES"))
    )
    (comp (ref "R68")
      (value "680k")
      (footprint "R1206")
      (description "0.25W/ 680kohm±1%")
      (fields (field (name "MPN") "RC1206FR-07680KL") (field (name "MFR") "Yageo"))
      (libsource (lib "RCL") (part "RES"))
    )
    (comp (ref "R69")
      (value "680k")
      (footprint "R1206")
      (description "0.25W/ 680kohm±1%")
      (fields (field (name "MPN") "RC1206FR-07680KL") (field (name "MFR") "Yageo"))
      (libsource (lib "RCL") (part "RES"))
    )
    (comp (ref "R70")
      (value "9.09k")
      (footprint "R0603")
      (description "0.1W/ 9.09kohm±1%")
      (fields (field (name "MPN") "RC0603FR-079K09L") (field (name "MFR") "Yageo"))
      (libsource (lib "RCL") (part "RES"))
    )
    (comp (ref "R71")
      (value "10k")
      (footprint "R0603")
      (description "0.1W/ 10kohm±1%")
      (fields (field (name "MPN") "RC0603FR-0710KL") (field (name "MFR") "Yageo"))
      (libsource (lib "RCL") (part "RES"))
    )
    (comp (ref "R72")
      (value "10k")
      (footprint "R0603")
      (description "0.1W/ 10kohm±1%")
      (fields (field (name "MPN") "RC0603FR-0710KL") (field (name "MFR") "Yageo"))
      (libsource (lib "RCL") (part "RES"))
    )
    (comp (ref "RV1")
      (value "B72210S2271K101")
      (footprint "VAR_B72220S2321K101")
      (description "Varistor (Voltage-Sensitive Resistor)")
      (fields (field (name "MFR") "EPCOS - TDK Electronics"))
      (libsource (lib "Miscellaneous Devices") (part "Res Varistor"))
    )
    (comp (ref "RV2")
      (value "MS22 12103")
      (footprint "MS22 12103")
      (description "Varistor (Voltage-Sensitive Resistor)")
      (fields (field (name "MFR") "Ametherm"))
      (libsource (lib "Miscellaneous Devices") (part "Res Varistor"))
    )
    (comp (ref "U1")
      (value "TMCS1100A1QDRQ1")
      (footprint "SOIC-8")
      (description "Board Mount Current Sensors Automotive, precisio n isolated current")
      (fields (field (name "MFR") "Texas Instruments"))
      (libsource (lib "Inverter_2kW") (part "TMCS1100A1QDRQ1"))
    )
    (comp (ref "U2")
      (value "TLP152(TPL,E")
      (footprint "OPTO_TLP2366(V4-TPL,E")
      (description "Isolated Gate Drivers Gate Drive Phcplr 3750 Vrms")
      (fields (field (name "MFR") "Toshiba"))
      (libsource (lib "Inverter_2kW") (part "TLP152(TPL,E"))
    )
    (comp (ref "U3")
      (value "TLP152(TPL,E")
      (footprint "OPTO_TLP2366(V4-TPL,E")
      (description "Isolated Gate Drivers Gate Drive Phcplr 3750 Vrms")
      (fields (field (name "MFR") "Toshiba"))
      (libsource (lib "Inverter_2kW") (part "TLP152(TPL,E"))
    )
    (comp (ref "U4")
      (value "MGJ2D121505SC")
      (footprint "MGJ2D121505SC")
      (description "Isolated DC/DC Converters - Through Hole 2W 12-15VIN 5VOUT DC/DC")
      (fields (field (name "MFR") "Murata"))
      (libsource (lib "Inverter_2kW") (part "MGJ2D121505SC"))
    )
    (comp (ref "U5")
      (value "MGJ2D121505SC")
      (footprint "MGJ2D121505SC")
      (description "Isolated DC/DC Converters - Through Hole 2W 12-15VIN 5VOUT DC/DC")
      (fields (field (name "MFR") "Murata"))
      (libsource (lib "Inverter_2kW") (part "MGJ2D121505SC"))
    )
    (comp (ref "U6")
      (value "TLV9004QDRQ1")
      (footprint "SOIC127P600X175-14N")
      (fields (field (name "MFR") "Texas Instruments"))
      (libsource (lib "Inverter_2kW") (part "TLV9004"))
    )
  )
  (nets
    (net (code "1") (name "+3.3V") (class "Default")
      (node (ref "C2") (pin "2") (pinfunction "2_2") (pintype "passive"))
      (node (ref "R20") (pin "1") (pinfunction "1_1") (pintype "passive"))
      (node (ref "R71") (pin "1") (pinfunction "1_1") (pintype "passive"))
      (node (ref "U1") (pin "8") (pinfunction "VS_8") (pintype "power_in"))
      (node (ref "U6") (pin "4") (pinfunction "VCC_4") (pintype "power_in"))
    )
    (net (code "2") (name "+12V") (class "Default")
      (node (ref "C26") (pin "2") (pinfunction "2_2") (pintype "passive"))
      (node (ref "C29") (pin "1") (pinfunction "1_1") (pintype "passive"))
      (node (ref "C43") (pin "2") (pinfunction "2_2") (pintype "passive"))
      (node (ref "C44") (pin "2") (pinfunction "2_2") (pintype "passive"))
      (node (ref "D10") (pin "C") (pinfunction "C_C") (pintype "passive"))
      (node (ref "D12") (pin "C") (pinfunction "C_C") (pintype "passive"))
      (node (ref "D14") (pin "C") (pinfunction "C_C") (pintype "passive"))
      (node (ref "D3") (pin "C") (pinfunction "C_C") (pintype "passive"))
      (node (ref "D9") (pin "C") (pinfunction "C_C") (pintype "passive"))
      (node (ref "K1") (pin "2") (pinfunction "A2_2") (pintype "passive"))
      (node (ref "K2") (pin "2") (pinfunction "A2_2") (pintype "passive"))
      (node (ref "K3") (pin "2") (pinfunction "A2_2") (pintype "passive"))
      (node (ref "K4") (pin "2") (pinfunction "A2_2") (pintype "passive"))
      (node (ref "PS1") (pin "3") (pinfunction "+VO_3") (pintype "output"))
      (node (ref "R2") (pin "2") (pinfunction "2_2") (pintype "passive"))
      (node (ref "U4") (pin "1") (pinfunction "+Vin_1") (pintype "passive"))
      (node (ref "U5") (pin "1") (pinfunction "+Vin_1") (pintype "passive"))
    )
    (net (code "3") (name "+12V_AC") (class "Default")
      (node (ref "C34") (pin "2") (pinfunction "2_2") (pintype "passive"))
      (node (ref "C35") (pin "1") (pinfunction "1_1") (pintype "passive"))
      (node (ref "D11") (pin "C") (pinfunction "C_C") (pintype "passive"))
      (node (ref "D13") (pin "C") (pinfunction "C_C") (pintype "passive"))
      (node (ref "D14") (pin "A") (pinfunction "A_A") (pintype "passive"))
      (node (ref "D18") (pin "C") (pinfunction "C_C") (pintype "passive"))
      (node (ref "K5") (pin "2") (pinfunction "A2_2") (pintype "passive"))
      (node (ref "K6") (pin "2") (pinfunction "A2_2") (pintype "passive"))
      (node (ref "K7") (pin "2") (pinfunction "A2_2") (pintype "passive"))
      (node (ref "K8") (pin "2") (pinfunction "A2_2") (pintype "passive"))
      (node (ref "L4") (pin "2") (pinfunction "2_2") (pintype "passive"))
      (node (ref "R27") (pin "2") (pinfunction "2_2") (pintype "passive"))
      (node (ref "R31") (pin "2") (pinfunction "2_2") (pintype "passive"))
      (node (ref "R33") (pin "2") (pinfunction "2_2") (pintype "passive"))
      (node (ref "R35") (pin "2") (pinfunction "2_2") (pintype "passive"))
    )
    (net (code "4") (name "+15V_1") (class "Default")
      (node (ref "C27") (pin "2") (pinfunction "2_2") (pintype "passive"))
      (node (ref "C28") (pin "2") (pinfunction "2_2") (pintype "passive"))
      (node (ref "C41") (pin "2") (pinfunction "2_2") (pintype "passive"))
      (node (ref "R28") (pin "2") (pinfunction "2_2") (pintype "passive"))
      (node (ref "U2") (pin "6") (pinfunction "Vcc_6") (pintype "passive"))
      (node (ref "U4") (pin "7") (pinfunction "+Vout_7") (pintype "passive"))
    )
    (net (code "5") (name "+15V_2") (class "Default")
      (node (ref "C36") (pin "2") (pinfunction "2_2") (pintype "passive"))
      (node (ref "C37") (pin "2") (pinfunction "2_2") (pintype "passive"))
      (node (ref "C42") (pin "2") (pinfunction "2_2") (pintype "passive"))
      (node (ref "R38") (pin "2") (pinfunction "2_2") (pintype "passive"))
      (node (ref "U3") (pin "6") (pinfunction "Vcc_6") (pintype "passive"))
      (node (ref "U5") (pin "7") (pinfunction "+Vout_7") (pintype "passive"))
    )
    (net (code "6") (name "+HV") (class "Default")
      (node (ref "C10") (pin "2") (pinfunction "2_2") (pintype "passive"))
      (node (ref "C5") (pin "1") (pinfunction "1_1") (pintype "passive"))
      (node (ref "C6") (pin "1") (pinfunction "1_1") (pintype "passive"))
      (node (ref "K2") (pin "4") (pinfunction "NO_4") (pintype "passive"))
      (node (ref "PS1") (pin "2") (pinfunction "+VIN_2") (pintype "input"))
      (node (ref "Q3") (pin "2") (pinfunction "D_2") (pintype "passive"))
      (node (ref "R11") (pin "2") (pinfunction "2_2") (pintype "passive"))
      (node (ref "R12") (pin "2") (pinfunction "2_2") (pintype "passive"))
      (node (ref "R13") (pin "2") (pinfunction "2_2") (pintype "passive"))
      (node (ref "R41") (pin "2") (pinfunction "2_2") (pintype "passive"))
      (node (ref "R9") (pin "2") (pinfunction "2_2") (pintype "passive"))
      (node (ref "RV2") (pin "2") (pinfunction "2_2") (pintype "passive"))
    )
    (net (code "7") (name "-5V_1") (class "Default")
      (node (ref "C27") (pin "1") (pinfunction "1_1") (pintype "passive"))
      (node (ref "C31") (pin "1") (pinfunction "1_1") (pintype "passive"))
      (node (ref "C45") (pin "1") (pinfunction "1_1") (pintype "passive"))
      (node (ref "D15") (pin "A") (pinfunction "A_A") (pintype "passive"))
      (node (ref "U2") (pin "4") (pinfunction "GND_4") (pintype "passive"))
      (node (ref "U4") (pin "5") (pinfunction "-Vout_5") (pintype "passive"))
    )
    (net (code "8") (name "-5V_2") (class "Default")
      (node (ref "C36") (pin "1") (pinfunction "1_1") (pintype "passive"))
      (node (ref "C39") (pin "1") (pinfunction "1_1") (pintype "passive"))
      (node (ref "C46") (pin "1") (pinfunction "1_1") (pintype "passive"))
      (node (ref "D19") (pin "A") (pinfunction "A_A") (pintype "passive"))
      (node (ref "U3") (pin "4") (pinfunction "GND_4") (pintype "passive"))
      (node (ref "U5") (pin "5") (pinfunction "-Vout_5") (pintype "passive"))
    )
    (net (code "9") (name "-HV") (class "Default")
      (node (ref "C10") (pin "1") (pinfunction "1_1") (pintype "passive"))
      (node (ref "C11") (pin "1") (pinfunction "1_1") (pintype "passive"))
      (node (ref "C12") (pin "1") (pinfunction "1_1") (pintype "passive"))
      (node (ref "C17") (pin "2") (pinfunction "2_2") (pintype "passive"))
      (node (ref "C18") (pin "2") (pinfunction "2_2") (pintype "passive"))
      (node (ref "C19") (pin "1") (pinfunction "1_1") (pintype "passive"))
      (node (ref "C20") (pin "1") (pinfunction "1_1") (pintype "passive"))
      (node (ref "C37") (pin "1") (pinfunction "1_1") (pintype "passive"))
      (node (ref "C39") (pin "2") (pinfunction "2_2") (pintype "passive"))
      (node (ref "C42") (pin "1") (pinfunction "1_1") (pintype "passive"))
      (node (ref "C46") (pin "2") (pinfunction "2_2") (pintype "passive"))
      (node (ref "D19") (pin "C") (pinfunction "C_C") (pintype "passive"))
      (node (ref "D8") (pin "C") (pinfunction "C_C") (pintype "passive"))
      (node (ref "HS1") (pin "1") (pinfunction "1_1") (pintype "passive"))
      (node (ref "HS1") (pin "2") (pinfunction "2_2") (pintype "passive"))
      (node (ref "HS2") (pin "1") (pinfunction "1_1") (pintype "passive"))
      (node (ref "HS2") (pin "2") (pinfunction "2_2") (pintype "passive"))
      (node (ref "L2") (pin "4") (pinfunction "4_4") (pintype "passive"))
      (node (ref "PS1") (pin "1") (pinfunction "-VIN_1") (pintype "input"))
      (node (ref "Q4") (pin "3") (pinfunction "S_3") (pintype "passive"))
      (node (ref "R18") (pin "1") (pinfunction "1_1") (pintype "passive"))
      (node (ref "R19") (pin "1") (pinfunction "1_1") (pintype "passive"))
      (node (ref "R38") (pin "1") (pinfunction "1_1") (pintype "passive"))
      (node (ref "R4") (pin "2") (pinfunction "2_2") (pintype "passive"))
      (node (ref "U5") (pin "6") (pinfunction "COM_6") (pintype "passive"))
    )
    (net (code "10") (name "/ACL_IN") (class "Default")
      (node (ref "K5") (pin "3") (pinfunction "C_3") (pintype "passive"))
      (node (ref "PS2") (pin "1") (pinfunction "AC(L)_1") (pintype "input"))
      (node (ref "R45") (pin "1") (pinfunction "1_1") (pintype "passive"))
    )
    (net (code "11") (name "/ACL_OUT") (class "Default")
      (node (ref "C14") (pin "2") (pinfunction "2_2") (pintype "passive"))
      (node (ref "L1") (pin "1") (pinfunction "1_1") (pintype "passive"))
      (node (ref "R49") (pin "1") (pinfunction "1_1") (pintype "passive"))
      (node (ref "RV1") (pin "1") (pinfunction "1_1") (pintype "passive"))
    )
    (net (code "12") (name "/ACN_IN") (class "Default")
      (node (ref "K7") (pin "3") (pinfunction "C_3") (pintype "passive"))
      (node (ref "PS2") (pin "2") (pinfunction "AC(N)_2") (pintype "input"))
      (node (ref "R56") (pin "1") (pinfunction "1_1") (pintype "passive"))
    )
    (net (code "13") (name "/ACN_OUT") (class "Default")
      (node (ref "C13") (pin "2") (pinfunction "2_2") (pintype "passive"))
      (node (ref "L1") (pin "2") (pinfunction "2_2") (pintype "passive"))
      (node (ref "R60") (pin "1") (pinfunction "1_1") (pintype "passive"))
      (node (ref "RV1") (pin "2") (pinfunction "2_2") (pintype "passive"))
    )
    (net (code "14") (name "/AC_bypass_relays_1") (class "Default")
      (node (ref "C25") (pin "2") (pinfunction "2_2") (pintype "passive"))
      (node (ref "Q7") (pin "1") (pinfunction "G_1") (pintype "passive"))
      (node (ref "R25") (pin "1") (pinfunction "1_1") (pintype "passive"))
      (node (ref "R29") (pin "1") (pinfunction "1_1") (pintype "passive"))
      (node (ref "R30") (pin "2") (pinfunction "2_2") (pintype "passive"))
    )
    (net (code "15") (name "/AC_bypass_relays_2") (class "Default")
      (node (ref "R32") (pin "1") (pinfunction "1_1") (pintype "passive"))
      (node (ref "R34") (pin "2") (pinfunction "2_2") (pintype "passive"))
    )
    (net (code "16") (name "/Gate_High") (class "Default")
      (node (ref "R26") (pin "1") (pinfunction "1_1") (pintype "passive"))
      (node (ref "R37") (pin "1") (pinfunction "1_1") (pintype "passive"))
      (node (ref "U3") (pin "3") (pinfunction "C_3") (pintype "passive"))
    )
    (net (code "17") (name "/Gate_Low") (class "Default")
      (node (ref "R36") (pin "1") (pinfunction "1_1") (pintype "passive"))
      (node (ref "U2") (pin "3") (pinfunction "C_3") (pintype "passive"))
    )
    (net (code "18") (name "/Grounding_relay") (class "Default")
      (node (ref "C23") (pin "2") (pinfunction "2_2") (pintype "passive"))
      (node (ref "Q5") (pin "1") (pinfunction "G_1") (pintype "passive"))
      (node (ref "R22") (pin "1") (pinfunction "1_1") (pintype "passive"))
    )
    (net (code "19") (name "/IFB_U") (class "Default")
      (node (ref "U1") (pin "7") (pinfunction "VOUT_7") (pintype "power_in"))
    )
    (net (code "20") (name "/Inverter_relays") (class "Default")
      (node (ref "R21") (pin "1") (pinfunction "1_1") (pintype "passive"))
    )
    (net (code "21") (name "/L+") (class "Default")
      (node (ref "C22") (pin "2") (pinfunction "2_2") (pintype "passive"))
      (node (ref "L2") (pin "2") (pinfunction "2_2") (pintype "passive"))
    )
    (net (code "22") (name "/L-") (class "Default")
      (node (ref "C21") (pin "2") (pinfunction "2_2") (pintype "passive"))
      (node (ref "L2") (pin "1") (pinfunction "1_1") (pintype "passive"))
    )
    (net (code "23") (name "/PEN") (class "Default")
      (node (ref "K4") (pin "3") (pinfunction "C_3") (pintype "passive"))
    )
    (net (code "24") (name "/Precharge_relay") (class "Default")
      (node (ref "C3") (pin "2") (pinfunction "2_2") (pintype "passive"))
      (node (ref "Q2") (pin "1") (pinfunction "G_1") (pintype "passive"))
      (node (ref "R6") (pin "1") (pinfunction "1_1") (pintype "passive"))
    )
    (net (code "25") (name "/Temp_sensor") (class "Default")
      (node (ref "R20") (pin "2") (pinfunction "2_2") (pintype "passive"))
      (node (ref "R23") (pin "1") (pinfunction "1_1") (pintype "passive"))
    )
    (net (code "26") (name "/VAC_IN_SENSE") (class "Default")
      (node (ref "R53") (pin "2") (pinfunction "2_2") (pintype "passive"))
    )
    (net (code "27") (name "/VAC_OUT_SENSE") (class "Default")
      (node (ref "R54") (pin "2") (pinfunction "2_2") (pintype "passive"))
    )
    (net (code "28") (name "/VDC_SENSE") (class "Default")
      (node (ref "C49") (pin "2") (pinfunction "2_2") (pintype "passive"))
      (node (ref "R44") (pin "1") (pinfunction "1_1") (pintype "passive"))
      (node (ref "R55") (pin "2") (pinfunction "2_2") (pintype "passive"))
    )
    (net (code "29") (name "/VFB_U") (class "Default")
      (node (ref "C7") (pin "2") (pinfunction "2_2") (pintype "passive"))
      (node (ref "R14") (pin "2") (pinfunction "2_2") (pintype "passive"))
      (node (ref "R8") (pin "1") (pinfunction "1_1") (pintype "passive"))
    )
    (net (code "30") (name "/VLA_REF_1") (class "Default")
      (node (ref "C47") (pin "2") (pinfunction "2_2") (pintype "passive"))
      (node (ref "C48") (pin "2") (pinfunction "2_2") (pintype "passive"))
      (node (ref "C54") (pin "2") (pinfunction "2_2") (pintype "passive"))
      (node (ref "R39") (pin "2") (pinfunction "2_2") (pintype "passive"))
      (node (ref "R40") (pin "2") (pinfunction "2_2") (pintype "passive"))
      (node (ref "U1") (pin "6") (pinfunction "VREF_6") (pintype "power_in"))
      (node (ref "U6") (pin "8") (pinfunction "OUT3_8") (pintype "output"))
      (node (ref "U6") (pin "9") (pinfunction "IN3-_9") (pintype "input"))
    )
    (net (code "31") (name "/V_Mid_SENSE") (class "Default")
      (node (ref "C52") (pin "2") (pinfunction "2_2") (pintype "passive"))
      (node (ref "R69") (pin "1") (pinfunction "1_1") (pintype "passive"))
      (node (ref "R70") (pin "2") (pinfunction "2_2") (pintype "passive"))
    )
    (net (code "32") (name "Earth") (class "Default")
      (node (ref "C13") (pin "1") (pinfunction "1_1") (pintype "passive"))
      (node (ref "C14") (pin "1") (pinfunction "1_1") (pintype "passive"))
      (node (ref "C15") (pin "1") (pinfunction "1_1") (pintype "passive"))
      (node (ref "C16") (pin "1") (pinfunction "1_1") (pintype "passive"))
      (node (ref "C21") (pin "1") (pinfunction "1_1") (pintype "passive"))
      (node (ref "C22") (pin "1") (pinfunction "1_1") (pintype "passive"))
    )
    (net (code "33") (name "GND") (class "Default")
      (node (ref "C2") (pin "1") (pinfunction "1_1") (pintype "passive"))
      (node (ref "C23") (pin "1") (pinfunction "1_1") (pintype "passive"))
      (node (ref "C24") (pin "1") (pinfunction "1_1") (pintype "passive"))
      (node (ref "C25") (pin "1") (pinfunction "1_1") (pintype "passive"))
      (node (ref "C26") (pin "1") (pinfunction "1_1") (pintype "passive"))
      (node (ref "C29") (pin "2") (pinfunction "2_2") (pintype "passive"))
      (node (ref "C3") (pin "1") (pinfunction "1_1") (pintype "passive"))
      (node (ref "C30") (pin "2") (pinfunction "2_2") (pintype "passive"))
      (node (ref "C32") (pin "2") (pinfunction "2_2") (pintype "passive"))
      (node (ref "C33") (pin "2") (pinfunction "2_2") (pintype "passive"))
      (node (ref "C34") (pin "1") (pinfunction "1_1") (pintype "passive"))
      (node (ref "C35") (pin "2") (pinfunction "2_2") (pintype "passive"))
      (node (ref "C40") (pin "1") (pinfunction "1_1") (pintype "passive"))
      (node (ref "C43") (pin "1") (pinfunction "1_1") (pintype "passive"))
      (node (ref "C44") (pin "1") (pinfunction "1_1") (pintype "passive"))
      (node (ref "C49") (pin "1") (pinfunction "1_1") (pintype "passive"))
      (node (ref "C52") (pin "1") (pinfunction "1_1") (pintype "passive"))
      (node (ref "C53") (pin "1") (pinfunction "1_1") (pintype "passive"))
      (node (ref "C54") (pin "1") (pinfunction "1_1") (pintype "passive"))
      (node (ref "C7") (pin "1") (pinfunction "1_1") (pintype "passive"))
      (node (ref "D12") (pin "A") (pinfunction "A_A") (pintype "passive"))
      (node (ref "D18") (pin "A") (pinfunction "A_A") (pintype "passive"))
      (node (ref "PS1") (pin "4") (pinfunction "-VO_4") (pintype "output"))
      (node (ref "PS2") (pin "5") (pinfunction "-VO_5") (pintype "output"))
      (node (ref "Q2") (pin "2") (pinfunction "S_2") (pintype "passive"))
      (node (ref "Q5") (pin "2") (pinfunction "S_2") (pintype "passive"))
      (node (ref "Q6") (pin "2") (pinfunction "S_2") (pintype "passive"))
      (node (ref "Q7") (pin "2") (pinfunction "S_2") (pintype "passive"))
      (node (ref "Q8") (pin "2") (pinfunction "S_2") (pintype "passive"))
      (node (ref "Q9") (pin "2") (pinfunction "S_2") (pintype "passive"))
      (node (ref "R14") (pin "1") (pinfunction "1_1") (pintype "passive"))
      (node (ref "R22") (pin "2") (pinfunction "2_2") (pintype "passive"))
      (node (ref "R23") (pin "2") (pinfunction "2_2") (pintype "passive"))
      (node (ref "R24") (pin "2") (pinfunction "2_2") (pintype "passive"))
      (node (ref "R25") (pin "2") (pinfunction "2_2") (pintype "passive"))
      (node (ref "R30") (pin "1") (pinfunction "1_1") (pintype "passive"))
      (node (ref "R34") (pin "1") (pinfunction "1_1") (pintype "passive"))
      (node (ref "R4") (pin "1") (pinfunction "1_1") (pintype "passive"))
      (node (ref "R55") (pin "1") (pinfunction "1_1") (pintype "passive"))
      (node (ref "R6") (pin "2") (pinfunction "2_2") (pintype "passive"))
      (node (ref "R70") (pin "1") (pinfunction "1_1") (pintype "passive"))
      (node (ref "R72") (pin "2") (pinfunction "2_2") (pintype "passive"))
      (node (ref "U1") (pin "5") (pinfunction "GND_5") (pintype "power_in"))
      (node (ref "U4") (pin "2") (pinfunction "-Vin_2") (pintype "passive"))
      (node (ref "U5") (pin "2") (pinfunction "-Vin_2") (pintype "passive"))
      (node (ref "U6") (pin "11") (pinfunction "GND_11") (pintype "power_in"))
    )
    (net (code "34") (name "MIDV") (class "Default")
      (node (ref "C28") (pin "1") (pinfunction "1_1") (pintype "passive"))
      (node (ref "C31") (pin "2") (pinfunction "2_2") (pintype "passive"))
      (node (ref "C41") (pin "1") (pinfunction "1_1") (pintype "passive"))
      (node (ref "C45") (pin "2") (pinfunction "2_2") (pintype "passive"))
      (node (ref "C8") (pin "1") (pinfunction "1_1") (pintype "passive"))
      (node (ref "C9") (pin "1") (pinfunction "1_1") (pintype "passive"))
      (node (ref "D15") (pin "C") (pinfunction "C_C") (pintype "passive"))
      (node (ref "D6") (pin "C") (pinfunction "C_C") (pintype "passive"))
      (node (ref "L3") (pin "1") (pinfunction "1_1") (pintype "passive"))
      (node (ref "Q3") (pin "3") (pinfunction "S_3") (pintype "passive"))
      (node (ref "Q4") (pin "2") (pinfunction "D_2") (pintype "passive"))
      (node (ref "R15") (pin "1") (pinfunction "1_1") (pintype "passive"))
      (node (ref "R16") (pin "2") (pinfunction "2_2") (pintype "passive"))
      (node (ref "R28") (pin "1") (pinfunction "1_1") (pintype "passive"))
      (node (ref "U4") (pin "6") (pinfunction "COM_6") (pintype "passive"))
    )
    (net (code "35") (name "Net-(C9-Pad2)") (class "Default")
      (node (ref "C9") (pin "2") (pinfunction "2_2") (pintype "passive"))
      (node (ref "R9") (pin "1") (pinfunction "1_1") (pintype "passive"))
    )
    (net (code "36") (name "Net-(C11-Pad2)") (class "Default")
      (node (ref "C11") (pin "2") (pinfunction "2_2") (pintype "passive"))
      (node (ref "R11") (pin "1") (pinfunction "1_1") (pintype "passive"))
    )
    (net (code "37") (name "Net-(C12-Pad2)") (class "Default")
      (node (ref "C12") (pin "2") (pinfunction "2_2") (pintype "passive"))
      (node (ref "R12") (pin "1") (pinfunction "1_1") (pintype "passive"))
    )
    (net (code "38") (name "Net-(C20-Pad2)") (class "Default")
      (node (ref "C20") (pin "2") (pinfunction "2_2") (pintype "passive"))
      (node (ref "R16") (pin "1") (pinfunction "1_1") (pintype "passive"))
    )
    (net (code "39") (name "Net-(D2-PadA)") (class "Default")
      (node (ref "D2") (pin "A") (pinfunction "A_A") (pintype "passive"))
      (node (ref "R2") (pin "1") (pinfunction "1_1") (pintype "passive"))
    )
    (net (code "40") (name "Net-(D4-A)") (class "Default")
      (node (ref "D4") (pin "3") (pinfunction "A_3") (pintype "passive"))
      (node (ref "K2") (pin "3") (pinfunction "C_3") (pintype "passive"))
      (node (ref "L2") (pin "3") (pinfunction "3_3") (pintype "passive"))
    )
    (net (code "41") (name "Net-(D4-C-Pad1)") (class "Default")
      (node (ref "D4") (pin "1") (pinfunction "C_1") (pintype "passive"))
      (node (ref "D4") (pin "4") (pinfunction "C_4") (pintype "passive"))
      (node (ref "RV2") (pin "1") (pinfunction "1_1") (pintype "passive"))
    )
    (net (code "42") (name "Net-(D5-PadA)") (class "Default")
      (node (ref "D5") (pin "A") (pinfunction "A_A") (pintype "passive"))
      (node (ref "D6") (pin "A") (pinfunction "A_A") (pintype "passive"))
    )
    (net (code "43") (name "Net-(D7-PadA)") (class "Default")
      (node (ref "D7") (pin "A") (pinfunction "A_A") (pintype "passive"))
      (node (ref "D8") (pin "A") (pinfunction "A_A") (pintype "passive"))
    )
    (net (code "44") (name "Net-(D16-PadA)") (class "Default")
      (node (ref "D16") (pin "A") (pinfunction "A_A") (pintype "passive"))
      (node (ref "R33") (pin "1") (pinfunction "1_1") (pintype "passive"))
    )
    (net (code "45") (name "Net-(D17-PadA)") (class "Default")
      (node (ref "D17") (pin "A") (pinfunction "A_A") (pintype "passive"))
      (node (ref "R35") (pin "1") (pinfunction "1_1") (pintype "passive"))
    )
    (net (code "46") (name "Net-(K1-A1)") (class "Default")
      (node (ref "D10") (pin "A") (pinfunction "A_A") (pintype "passive"))
      (node (ref "D2") (pin "C") (pinfunction "C_C") (pintype "passive"))
      (node (ref "K1") (pin "1") (pinfunction "A1_1") (pintype "passive"))
      (node (ref "K3") (pin "1") (pinfunction "A1_1") (pintype "passive"))
      (node (ref "Q6") (pin "3") (pinfunction "D_3") (pintype "passive"))
    )
    (net (code "47") (name "Net-(K1-C)") (class "Default")
      (node (ref "C4") (pin "2") (pinfunction "2_2") (pintype "passive"))
      (node (ref "K1") (pin "3") (pinfunction "C_3") (pintype "passive"))
      (node (ref "R3") (pin "2") (pinfunction "2_2") (pintype "passive"))
      (node (ref "U1") (pin "3") (pinfunction "IN-_3") (pintype "output"))
      (node (ref "U1") (pin "4") (pinfunction "IN-_4") (pintype "output"))
    )
    (net (code "48") (name "Net-(K1-NO)") (class "Default")
      (node (ref "C16") (pin "2") (pinfunction "2_2") (pintype "passive"))
      (node (ref "K1") (pin "4") (pinfunction "NO_4") (pintype "passive"))
      (node (ref "K6") (pin "4") (pinfunction "NO_4") (pintype "passive"))
      (node (ref "L1") (pin "4") (pinfunction "4_4") (pintype "passive"))
    )
    (net (code "49") (name "Net-(K2-A1)") (class "Default")
      (node (ref "D3") (pin "A") (pinfunction "A_A") (pintype "passive"))
      (node (ref "K2") (pin "1") (pinfunction "A1_1") (pintype "passive"))
      (node (ref "Q2") (pin "3") (pinfunction "D_3") (pintype "passive"))
    )
    (net (code "50") (name "Net-(K3-NO)") (class "Default")
      (node (ref "C15") (pin "2") (pinfunction "2_2") (pintype "passive"))
      (node (ref "K3") (pin "4") (pinfunction "NO_4") (pintype "passive"))
      (node (ref "K8") (pin "4") (pinfunction "NO_4") (pintype "passive"))
      (node (ref "L1") (pin "3") (pinfunction "3_3") (pintype "passive"))
    )
    (net (code "51") (name "Net-(K4-A1)") (class "Default")
      (node (ref "D9") (pin "A") (pinfunction "A_A") (pintype "passive"))
      (node (ref "K4") (pin "1") (pinfunction "A1_1") (pintype "passive"))
      (node (ref "Q5") (pin "3") (pinfunction "D_3") (pintype "passive"))
    )
    (net (code "52") (name "Net-(K5-A1)") (class "Default")
      (node (ref "D11") (pin "A") (pinfunction "A_A") (pintype "passive"))
      (node (ref "D16") (pin "C") (pinfunction "C_C") (pintype "passive"))
      (node (ref "K5") (pin "1") (pinfunction "A1_1") (pintype "passive"))
      (node (ref "K7") (pin "1") (pinfunction "A1_1") (pintype "passive"))
      (node (ref "Q8") (pin "3") (pinfunction "D_3") (pintype "passive"))
    )
    (net (code "53") (name "Net-(K5-NO)") (class "Default")
      (node (ref "K5") (pin "4") (pinfunction "NO_4") (pintype "passive"))
      (node (ref "K6") (pin "3") (pinfunction "C_3") (pintype "passive"))
    )
    (net (code "54") (name "Net-(K6-A1)") (class "Default")
      (node (ref "D13") (pin "A") (pinfunction "A_A") (pintype "passive"))
      (node (ref "D17") (pin "C") (pinfunction "C_C") (pintype "passive"))
      (node (ref "K6") (pin "1") (pinfunction "A1_1") (pintype "passive"))
      (node (ref "K8") (pin "1") (pinfunction "A1_1") (pintype "passive"))
      (node (ref "Q9") (pin "3") (pinfunction "D_3") (pintype "passive"))
    )
    (net (code "55") (name "Net-(K7-NO)") (class "Default")
      (node (ref "K7") (pin "4") (pinfunction "NO_4") (pintype "passive"))
      (node (ref "K8") (pin "3") (pinfunction "C_3") (pintype "passive"))
    )
    (net (code "56") (name "Net-(L3-Pad2)") (class "Default")
      (node (ref "L3") (pin "2") (pinfunction "2_2") (pintype "passive"))
      (node (ref "U1") (pin "1") (pinfunction "IN+_1") (pintype "input"))
      (node (ref "U1") (pin "2") (pinfunction "IN+_2") (pintype "input"))
    )
    (net (code "57") (name "Net-(PS2-+V(CAP))") (class "Default")
      (node (ref "C38") (pin "1") (pinfunction "1_1") (pintype "passive"))
      (node (ref "PS2") (pin "3") (pinfunction "+V(CAP)_3") (pintype "passive"))
    )
    (net (code "58") (name "Net-(PS2-+VO)") (class "Default")
      (node (ref "C33") (pin "1") (pinfunction "1_1") (pintype "passive"))
      (node (ref "L4") (pin "1") (pinfunction "1_1") (pintype "passive"))
      (node (ref "PS2") (pin "6") (pinfunction "+VO_6") (pintype "output"))
    )
    (net (code "59") (name "Net-(PS2--V(CAP))") (class "Default")
      (node (ref "C38") (pin "2") (pinfunction "2_2") (pintype "passive"))
      (node (ref "C40") (pin "2") (pinfunction "2_2") (pintype "passive"))
      (node (ref "PS2") (pin "4") (pinfunction "-V(CAP)_4") (pintype "passive"))
    )
    (net (code "60") (name "Net-(Q3-G)") (class "Default")
      (node (ref "C8") (pin "2") (pinfunction "2_2") (pintype "passive"))
      (node (ref "D5") (pin "C") (pinfunction "C_C") (pintype "passive"))
      (node (ref "Q3") (pin "1") (pinfunction "G_1") (pintype "passive"))
      (node (ref "R10") (pin "1") (pinfunction "1_1") (pintype "passive"))
      (node (ref "R15") (pin "2") (pinfunction "2_2") (pintype "passive"))
    )
    (net (code "61") (name "Net-(Q4-G)") (class "Default")
      (node (ref "C19") (pin "2") (pinfunction "2_2") (pintype "passive"))
      (node (ref "D7") (pin "C") (pinfunction "C_C") (pintype "passive"))
      (node (ref "Q4") (pin "1") (pinfunction "G_1") (pintype "passive"))
      (node (ref "R17") (pin "1") (pinfunction "1_1") (pintype "passive"))
      (node (ref "R19") (pin "2") (pinfunction "2_2") (pintype "passive"))
    )
    (net (code "62") (name "Net-(Q6-G)") (class "Default")
      (node (ref "C24") (pin "2") (pinfunction "2_2") (pintype "passive"))
      (node (ref "Q6") (pin "1") (pinfunction "G_1") (pintype "passive"))
      (node (ref "Q7") (pin "3") (pinfunction "D_3") (pintype "passive"))
      (node (ref "R21") (pin "2") (pinfunction "2_2") (pintype "passive"))
      (node (ref "R24") (pin "1") (pinfunction "1_1") (pintype "passive"))
    )
    (net (code "63") (name "Net-(Q8-G)") (class "Default")
      (node (ref "C30") (pin "1") (pinfunction "1_1") (pintype "passive"))
      (node (ref "Q8") (pin "1") (pinfunction "G_1") (pintype "passive"))
      (node (ref "R27") (pin "1") (pinfunction "1_1") (pintype "passive"))
      (node (ref "R29") (pin "2") (pinfunction "2_2") (pintype "passive"))
    )
    (net (code "64") (name "Net-(Q9-G)") (class "Default")
      (node (ref "C32") (pin "1") (pinfunction "1_1") (pintype "passive"))
      (node (ref "Q9") (pin "1") (pinfunction "G_1") (pintype "passive"))
      (node (ref "R31") (pin "1") (pinfunction "1_1") (pintype "passive"))
      (node (ref "R32") (pin "2") (pinfunction "2_2") (pintype "passive"))
    )
    (net (code "65") (name "Net-(R3-Pad1)") (class "Default")
      (node (ref "R3") (pin "1") (pinfunction "1_1") (pintype "passive"))
      (node (ref "R5") (pin "2") (pinfunction "2_2") (pintype "passive"))
    )
    (net (code "66") (name "Net-(R5-Pad1)") (class "Default")
      (node (ref "R5") (pin "1") (pinfunction "1_1") (pintype "passive"))
      (node (ref "R7") (pin "2") (pinfunction "2_2") (pintype "passive"))
    )
    (net (code "67") (name "Net-(R7-Pad1)") (class "Default")
      (node (ref "R7") (pin "1") (pinfunction "1_1") (pintype "passive"))
      (node (ref "R8") (pin "2") (pinfunction "2_2") (pintype "passive"))
    )
    (net (code "68") (name "Net-(R41-Pad1)") (class "Default")
      (node (ref "R41") (pin "1") (pinfunction "1_1") (pintype "passive"))
      (node (ref "R42") (pin "2") (pinfunction "2_2") (pintype "passive"))
    )
    (net (code "69") (name "Net-(R42-Pad1)") (class "Default")
      (node (ref "R42") (pin "1") (pinfunction "1_1") (pintype "passive"))
      (node (ref "R43") (pin "2") (pinfunction "2_2") (pintype "passive"))
    )
    (net (code "70") (name "Net-(R43-Pad1)") (class "Default")
      (node (ref "R43") (pin "1") (pinfunction "1_1") (pintype "passive"))
      (node (ref "R44") (pin "2") (pinfunction "2_2") (pintype "passive"))
    )
    (net (code "71") (name "Net-(R45-Pad2)") (class "Default")
      (node (ref "R45") (pin "2") (pinfunction "2_2") (pintype "passive"))
      (node (ref "R46") (pin "1") (pinfunction "1_1") (pintype "passive"))
    )
    (net (code "72") (name "Net-(R46-Pad2)") (class "Default")
      (node (ref "R46") (pin "2") (pinfunction "2_2") (pintype "passive"))
      (node (ref "R47") (pin "1") (pinfunction "1_1") (pintype "passive"))
    )
    (net (code "73") (name "Net-(R47-Pad2)") (class "Default")
      (node (ref "R47") (pin "2") (pinfunction "2_2") (pintype "passive"))
      (node (ref "R48") (pin "1") (pinfunction "1_1") (pintype "passive"))
    )
    (net (code "74") (name "Net-(R49-Pad2)") (class "Default")
      (node (ref "R49") (pin "2") (pinfunction "2_2") (pintype "passive"))
      (node (ref "R50") (pin "1") (pinfunction "1_1") (pintype "passive"))
    )
    (net (code "75") (name "Net-(R50-Pad2)") (class "Default")
      (node (ref "R50") (pin "2") (pinfunction "2_2") (pintype "passive"))
      (node (ref "R51") (pin "1") (pinfunction "1_1") (pintype "passive"))
    )
    (net (code "76") (name "Net-(R51-Pad2)") (class "Default")
      (node (ref "R51") (pin "2") (pinfunction "2_2") (pintype "passive"))
      (node (ref "R52") (pin "1") (pinfunction "1_1") (pintype "passive"))
    )
    (net (code "77") (name "Net-(R56-Pad2)") (class "Default")
      (node (ref "R56") (pin "2") (pinfunction "2_2") (pintype "passive"))
      (node (ref "R57") (pin "1") (pinfunction "1_1") (pintype "passive"))
    )
    (net (code "78") (name "Net-(R57-Pad2)") (class "Default")
      (node (ref "R57") (pin "2") (pinfunction "2_2") (pintype "passive"))
      (node (ref "R58") (pin "1") (pinfunction "1_1") (pintype "passive"))
    )
    (net (code "79") (name "Net-(R58-Pad2)") (class "Default")
      (node (ref "R58") (pin "2") (pinfunction "2_2") (pintype "passive"))
      (node (ref "R59") (pin "1") (pinfunction "1_1") (pintype "passive"))
    )
    (net (code "80") (name "Net-(R60-Pad2)") (class "Default")
      (node (ref "R60") (pin "2") (pinfunction "2_2") (pintype "passive"))
      (node (ref "R61") (pin "1") (pinfunction "1_1") (pintype "passive"))
    )
    (net (code "81") (name "Net-(R61-Pad2)") (class "Default")
      (node (ref "R61") (pin "2") (pinfunction "2_2") (pintype "passive"))
      (node (ref "R62") (pin "1") (pinfunction "1_1") (pintype "passive"))
    )
    (net (code "82") (name "Net-(R62-Pad2)") (class "Default")
      (node (ref "R62") (pin "2") (pinfunction "2_2") (pintype "passive"))
      (node (ref "R63") (pin "1") (pinfunction "1_1") (pintype "passive"))
    )
    (net (code "83") (name "Net-(R66-Pad1)") (class "Default")
      (node (ref "R66") (pin "1") (pinfunction "1_1") (pintype "passive"))
      (node (ref "R67") (pin "2") (pinfunction "2_2") (pintype "passive"))
    )
    (net (code "84") (name "Net-(R67-Pad1)") (class "Default")
      (node (ref "R67") (pin "1") (pinfunction "1_1") (pintype "passive"))
      (node (ref "R68") (pin "2") (pinfunction "2_2") (pintype "passive"))
    )
    (net (code "85") (name "Net-(R68-Pad1)") (class "Default")
      (node (ref "R68") (pin "1") (pinfunction "1_1") (pintype "passive"))
      (node (ref "R69") (pin "2") (pinfunction "2_2") (pintype "passive"))
    )
    (net (code "86") (name "Net-(U2-A)") (class "Default")
      (node (ref "R26") (pin "2") (pinfunction "2_2") (pintype "passive"))
      (node (ref "U2") (pin "1") (pinfunction "A_1") (pintype "passive"))
    )
    (net (code "87") (name "Net-(U2-Vo)") (class "Default")
      (node (ref "R10") (pin "2") (pinfunction "2_2") (pintype "passive"))
      (node (ref "U2") (pin "5") (pinfunction "Vo_5") (pintype "passive"))
    )
    (net (code "88") (name "Net-(U3-A)") (class "Default")
      (node (ref "R36") (pin "2") (pinfunction "2_2") (pintype "passive"))
      (node (ref "R37") (pin "2") (pinfunction "2_2") (pintype "passive"))
      (node (ref "U3") (pin "1") (pinfunction "A_1") (pintype "passive"))
    )
    (net (code "89") (name "Net-(U3-Vo)") (class "Default")
      (node (ref "R17") (pin "2") (pinfunction "2_2") (pintype "passive"))
      (node (ref "U3") (pin "5") (pinfunction "Vo_5") (pintype "passive"))
    )
    (net (code "90") (name "Net-(U6A-IN1+)") (class "Default")
      (node (ref "C47") (pin "1") (pinfunction "1_1") (pintype "passive"))
      (node (ref "R39") (pin "1") (pinfunction "1_1") (pintype "passive"))
      (node (ref "R48") (pin "2") (pinfunction "2_2") (pintype "passive"))
      (node (ref "U6") (pin "3") (pinfunction "IN1+_3") (pintype "input"))
    )
    (net (code "91") (name "Net-(U6A-IN1-)") (class "Default")
      (node (ref "C50") (pin "2") (pinfunction "2_2") (pintype "passive"))
      (node (ref "R59") (pin "2") (pinfunction "2_2") (pintype "passive"))
      (node (ref "R64") (pin "1") (pinfunction "1_1") (pintype "passive"))
      (node (ref "U6") (pin "2") (pinfunction "IN1-_2") (pintype "input"))
    )
    (net (code "92") (name "Net-(U6A-OUT1)") (class "Default")
      (node (ref "C50") (pin "1") (pinfunction "1_1") (pintype "passive"))
      (node (ref "R53") (pin "1") (pinfunction "1_1") (pintype "passive"))
      (node (ref "R64") (pin "2") (pinfunction "2_2") (pintype "passive"))
      (node (ref "U6") (pin "1") (pinfunction "OUT1_1") (pintype "output"))
    )
    (net (code "93") (name "Net-(U6B-IN2+)") (class "Default")
      (node (ref "C48") (pin "1") (pinfunction "1_1") (pintype "passive"))
      (node (ref "R40") (pin "1") (pinfunction "1_1") (pintype "passive"))
      (node (ref "R52") (pin "2") (pinfunction "2_2") (pintype "passive"))
      (node (ref "U6") (pin "5") (pinfunction "IN2+_5") (pintype "input"))
    )
    (net (code "94") (name "Net-(U6B-IN2-)") (class "Default")
      (node (ref "C51") (pin "2") (pinfunction "2_2") (pintype "passive"))
      (node (ref "R63") (pin "2") (pinfunction "2_2") (pintype "passive"))
      (node (ref "R65") (pin "1") (pinfunction "1_1") (pintype "passive"))
      (node (ref "U6") (pin "6") (pinfunction "IN2-_6") (pintype "input"))
    )
    (net (code "95") (name "Net-(U6B-OUT2)") (class "Default")
      (node (ref "C51") (pin "1") (pinfunction "1_1") (pintype "passive"))
      (node (ref "R54") (pin "1") (pinfunction "1_1") (pintype "passive"))
      (node (ref "R65") (pin "2") (pinfunction "2_2") (pintype "passive"))
      (node (ref "U6") (pin "7") (pinfunction "OUT2_7") (pintype "output"))
    )
    (net (code "96") (name "Net-(U6C-IN3+)") (class "Default")
      (node (ref "C53") (pin "2") (pinfunction "2_2") (pintype "passive"))
      (node (ref "R71") (pin "2") (pinfunction "2_2") (pintype "passive"))
      (node (ref "R72") (pin "1") (pinfunction "1_1") (pintype "passive"))
      (node (ref "U6") (pin "10") (pinfunction "IN3+_10") (pintype "input"))
    )
    (net (code "97") (name "V_Mid") (class "Default")
      (node (ref "C17") (pin "1") (pinfunction "1_1") (pintype "passive"))
      (node (ref "C18") (pin "1") (pinfunction "1_1") (pintype "passive"))
      (node (ref "C4") (pin "1") (pinfunction "1_1") (pintype "passive"))
      (node (ref "C5") (pin "2") (pinfunction "2_2") (pintype "passive"))
      (node (ref "C6") (pin "2") (pinfunction "2_2") (pintype "passive"))
      (node (ref "K3") (pin "3") (pinfunction "C_3") (pintype "passive"))
      (node (ref "K4") (pin "4") (pinfunction "NO_4") (pintype "passive"))
      (node (ref "R13") (pin "1") (pinfunction "1_1") (pintype "passive"))
      (node (ref "R18") (pin "2") (pinfunction "2_2") (pintype "passive"))
      (node (ref "R66") (pin "2") (pinfunction "2_2") (pintype "passive"))
    )
    (net (code "98") (name "unconnected-(U6D-IN4+-Pad12)") (class "Default")
      (node (ref "U6") (pin "12") (pinfunction "IN4+_12") (pintype "input"))
    )
    (net (code "99") (name "unconnected-(U6D-IN4--Pad13)") (class "Default")
      (node (ref "U6") (pin "13") (pinfunction "IN4-_13") (pintype "input"))
    )
    (net (code "100") (name "unconnected-(U6D-OUT4-Pad14)") (class "Default")
      (node (ref "U6") (pin "14") (pinfunction "OUT4_14") (pintype "output"))
    )
  )
)
